# controller.net
KiCad netlist of a schematic drawn in EAGLE
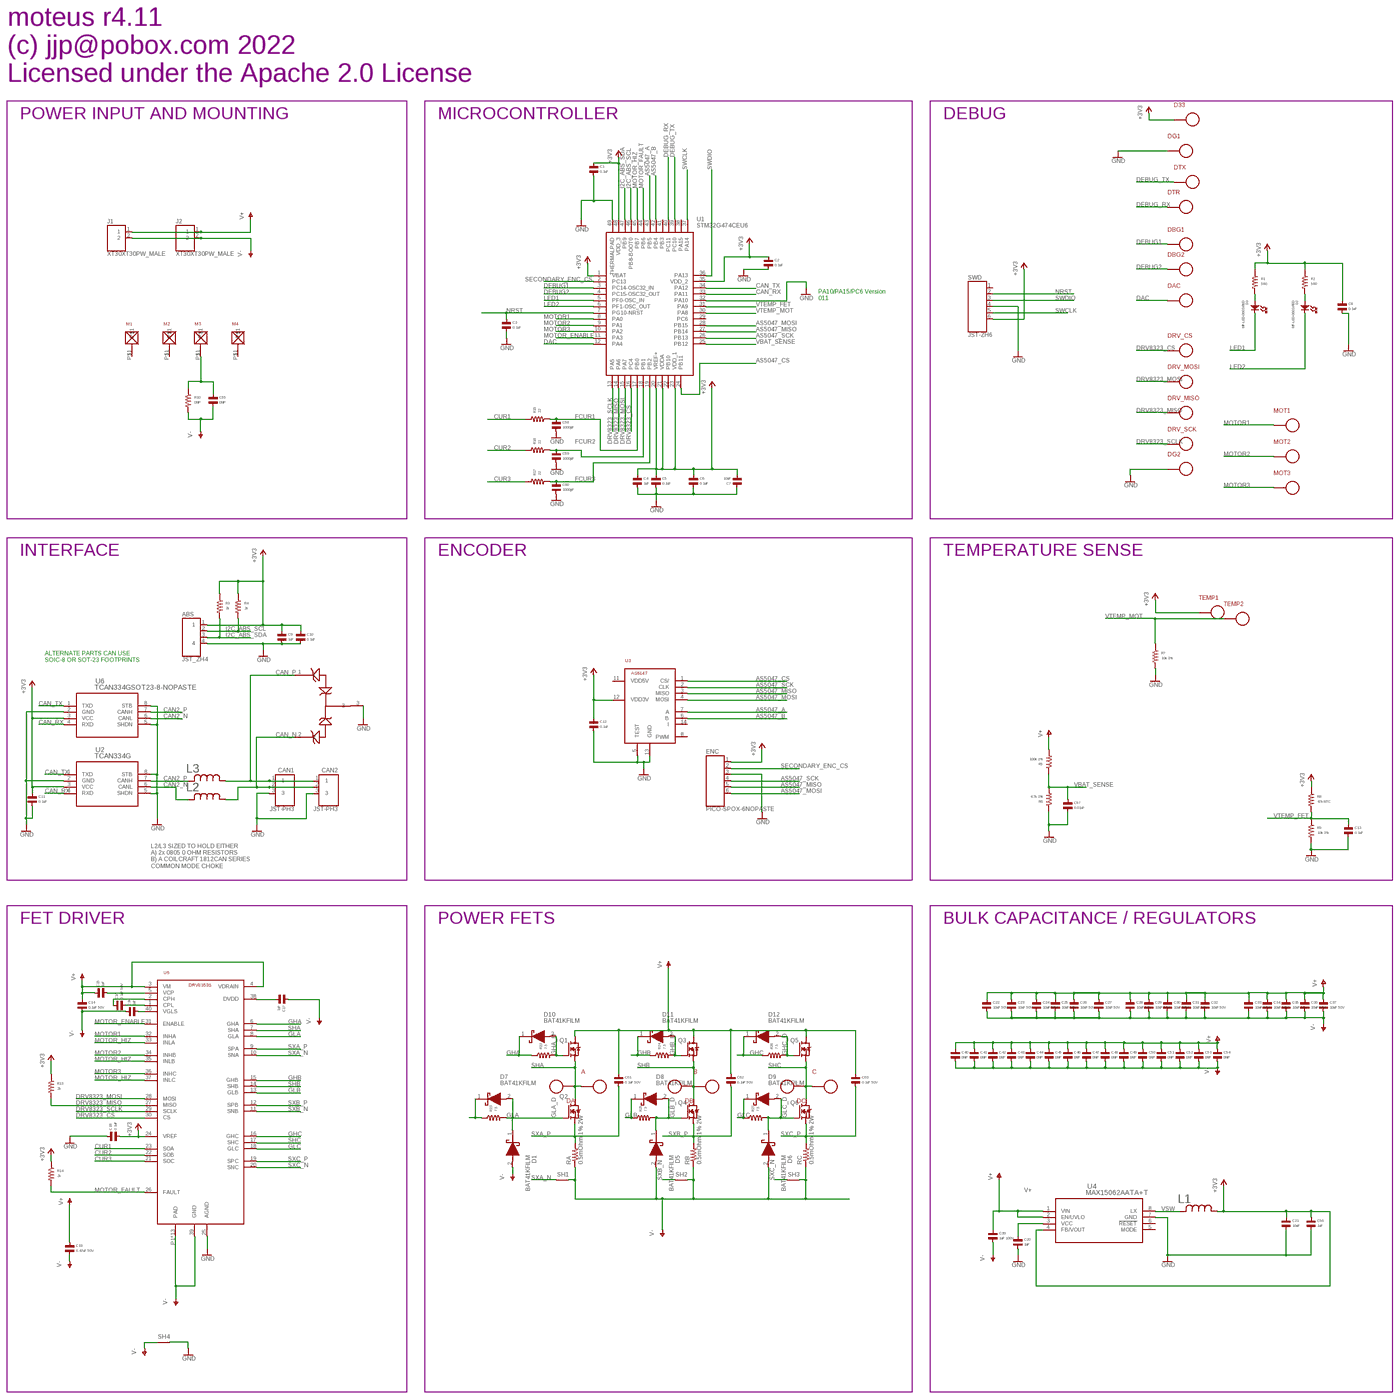
[diagram p0: schematic, sheet 1, overview]
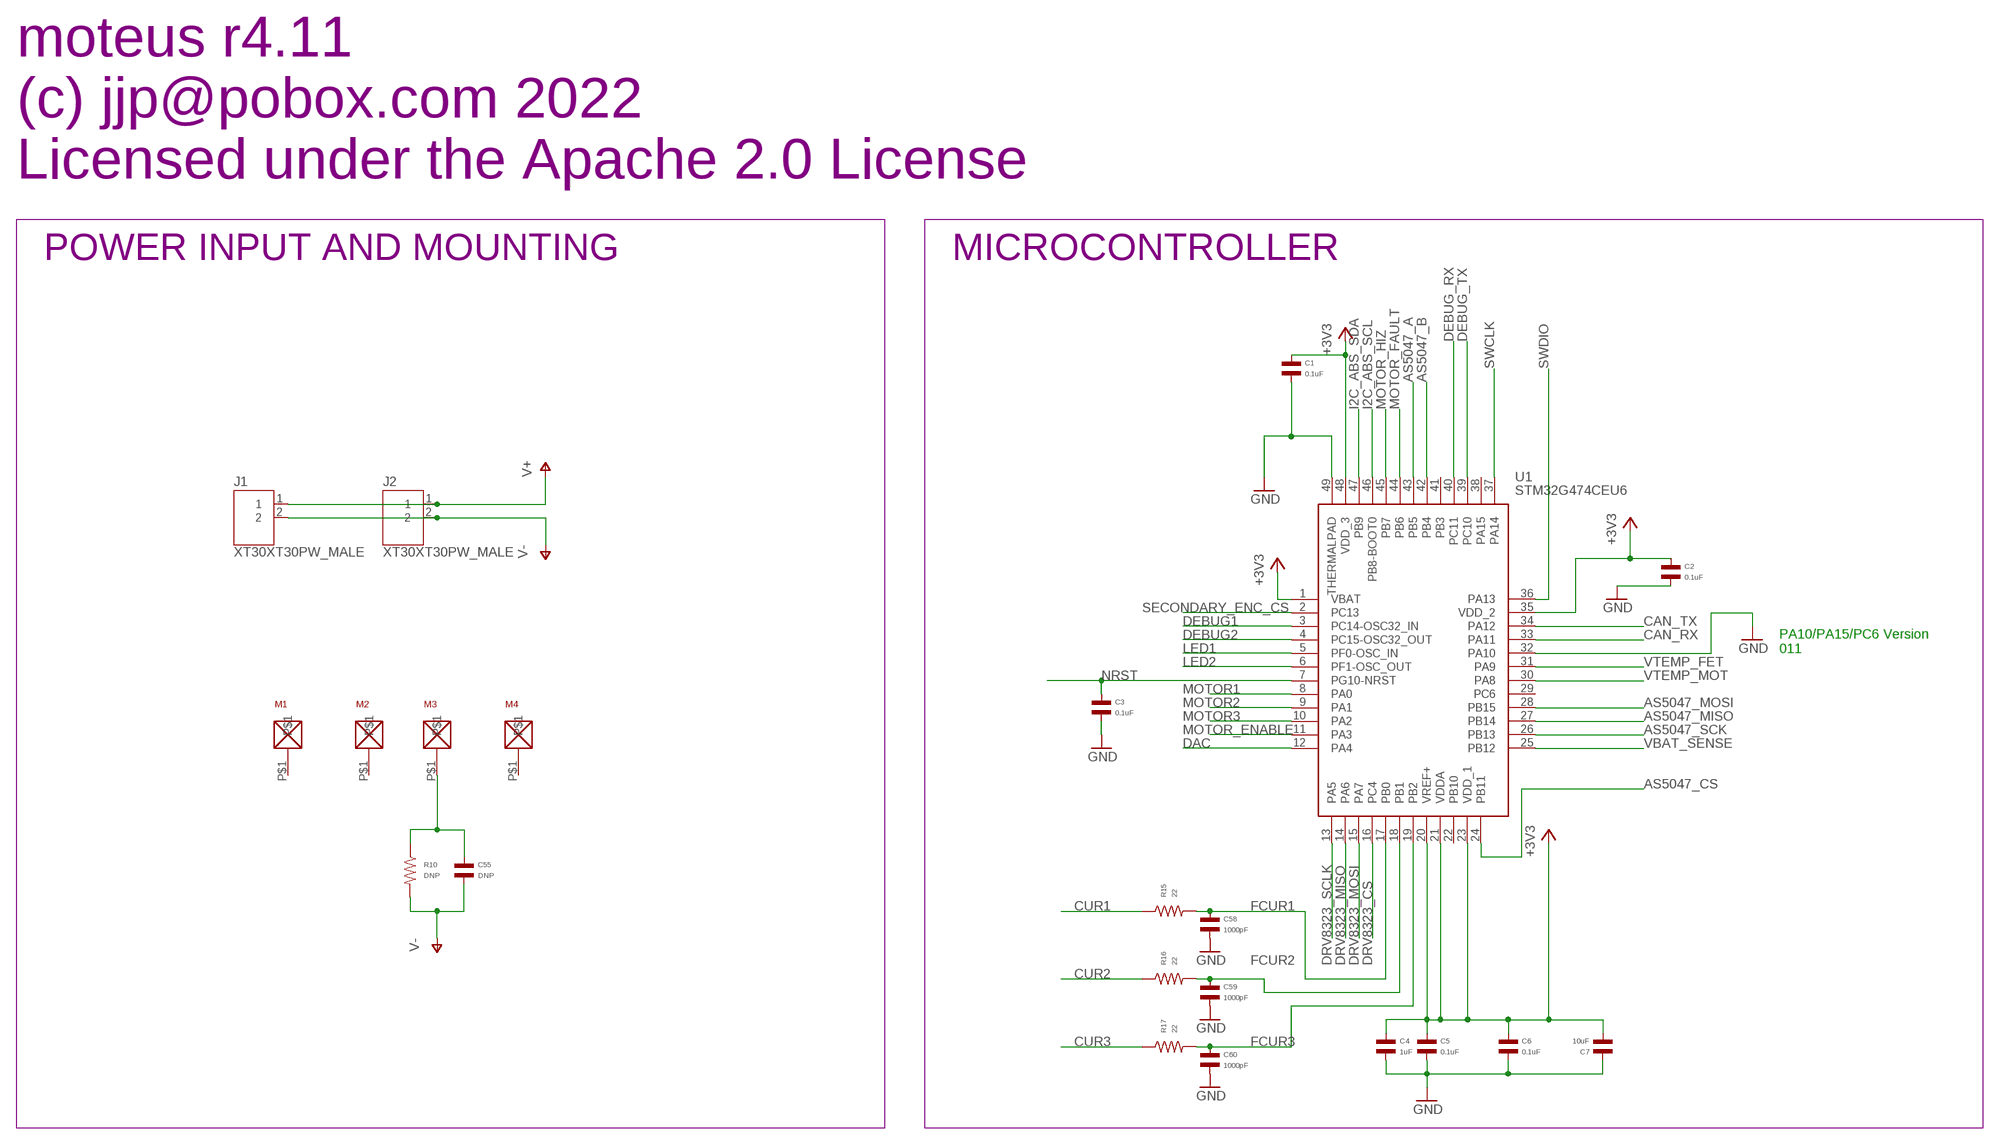
[diagram p1: schematic, sheet 1, part 1 of 4]
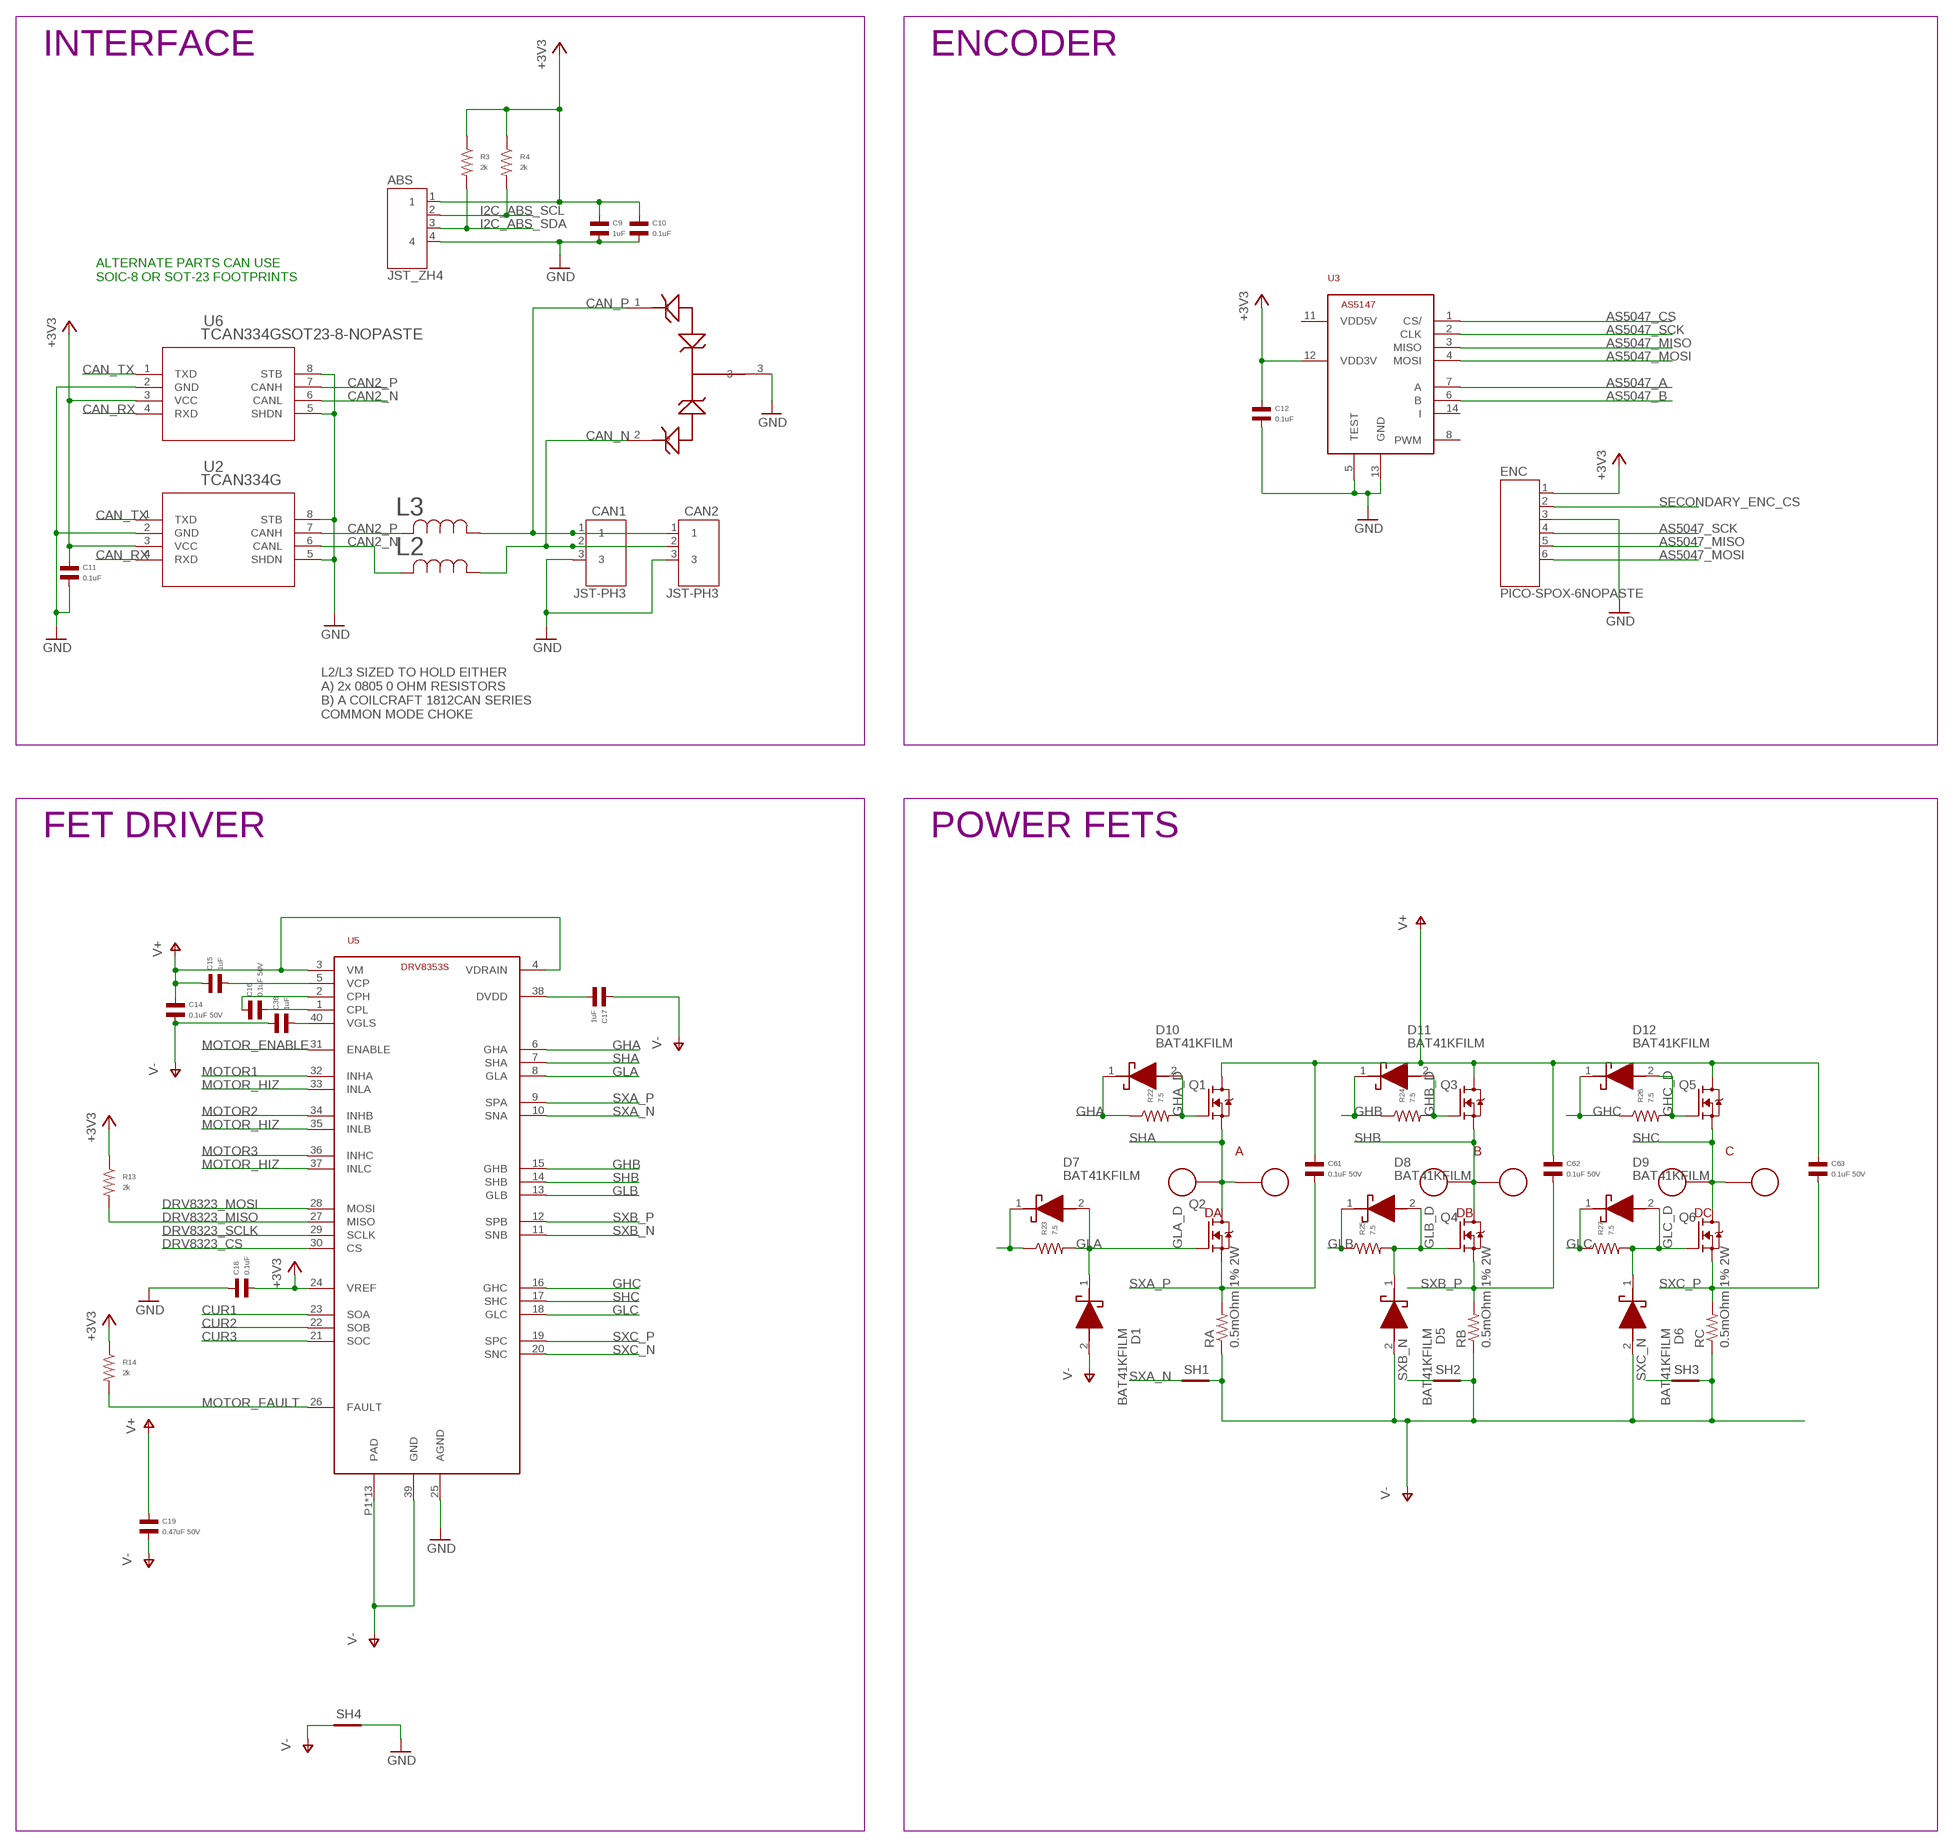
[diagram p2: schematic, sheet 1, part 2 of 4]
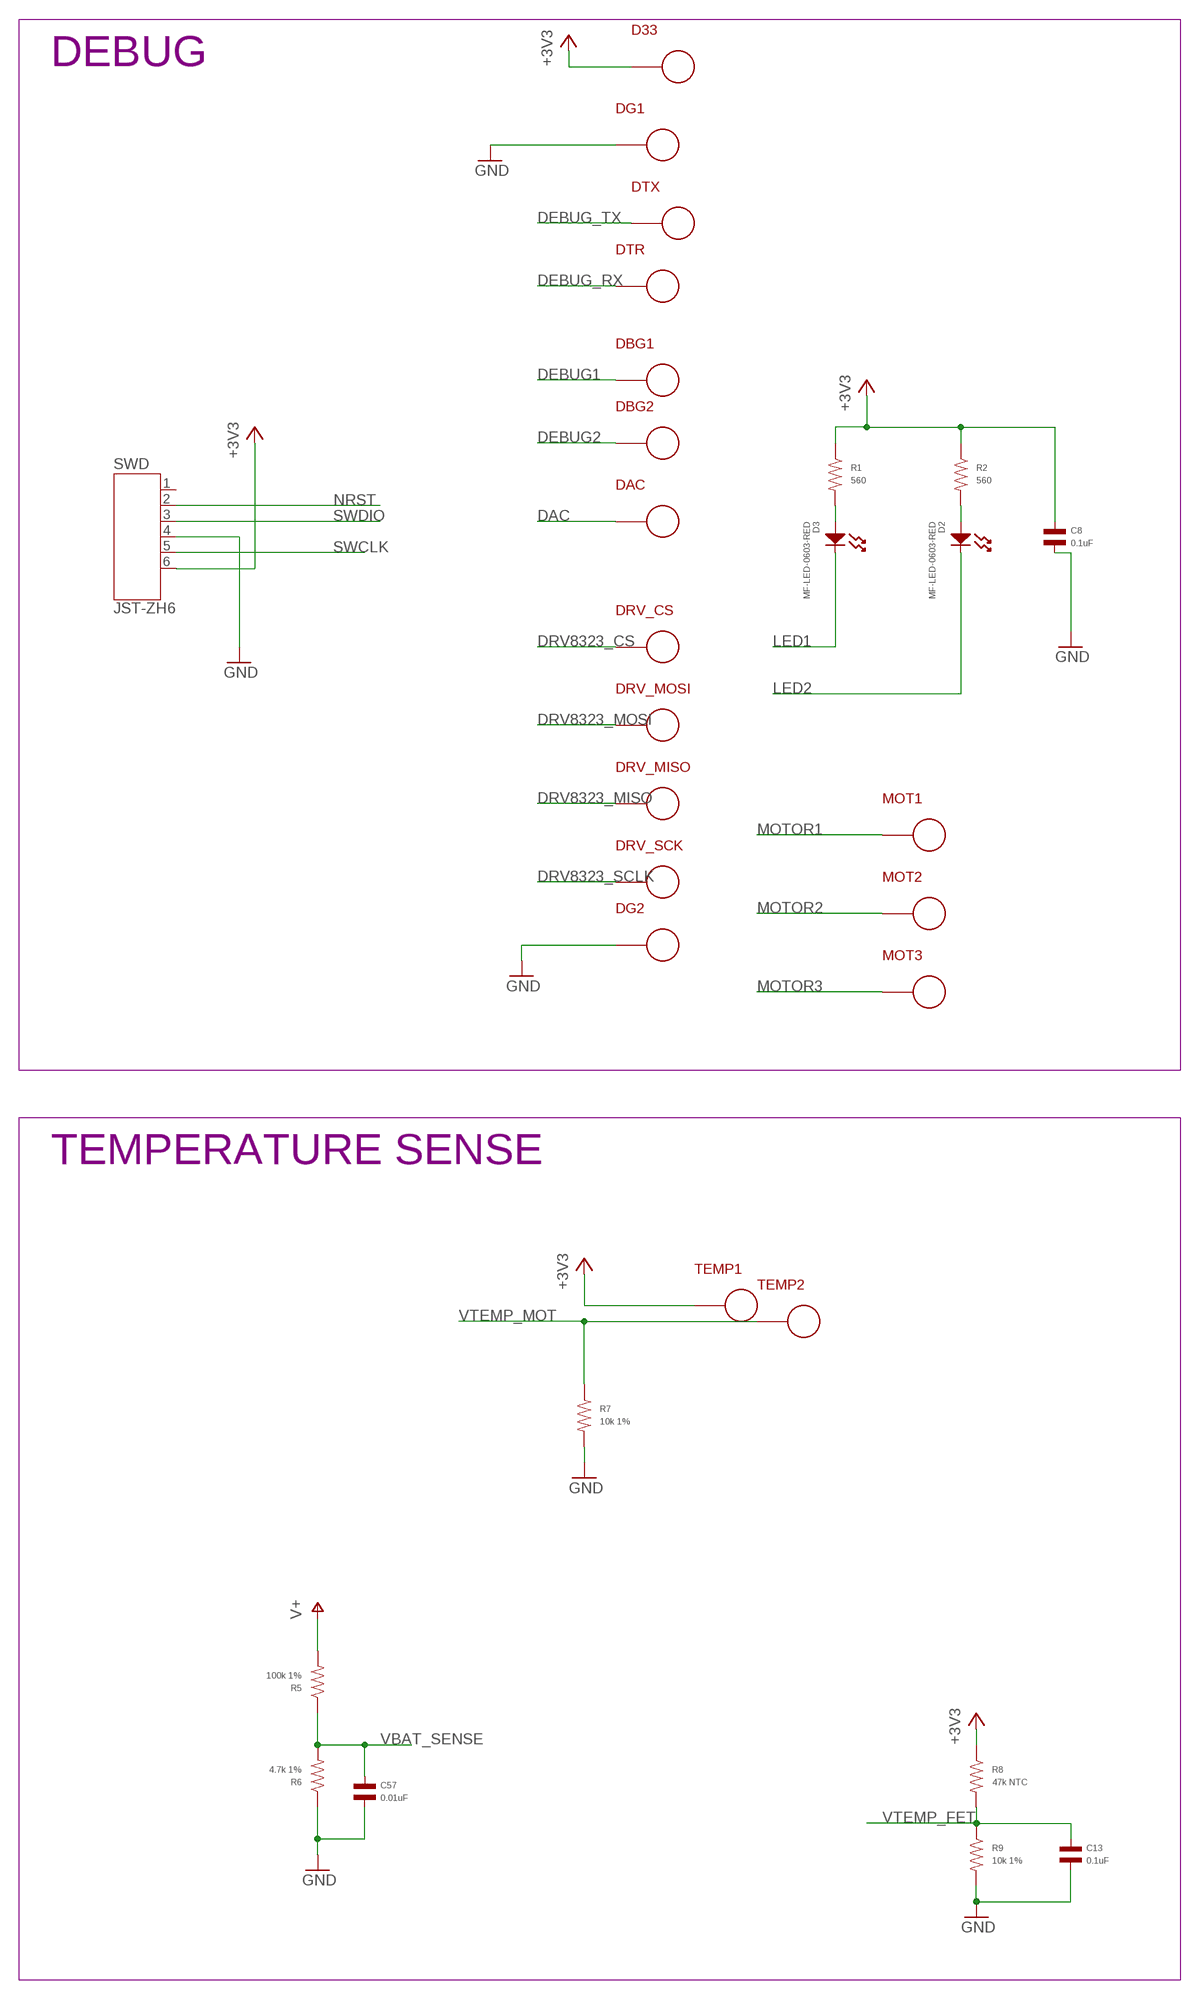
[diagram p3: schematic, sheet 1, part 3 of 4]
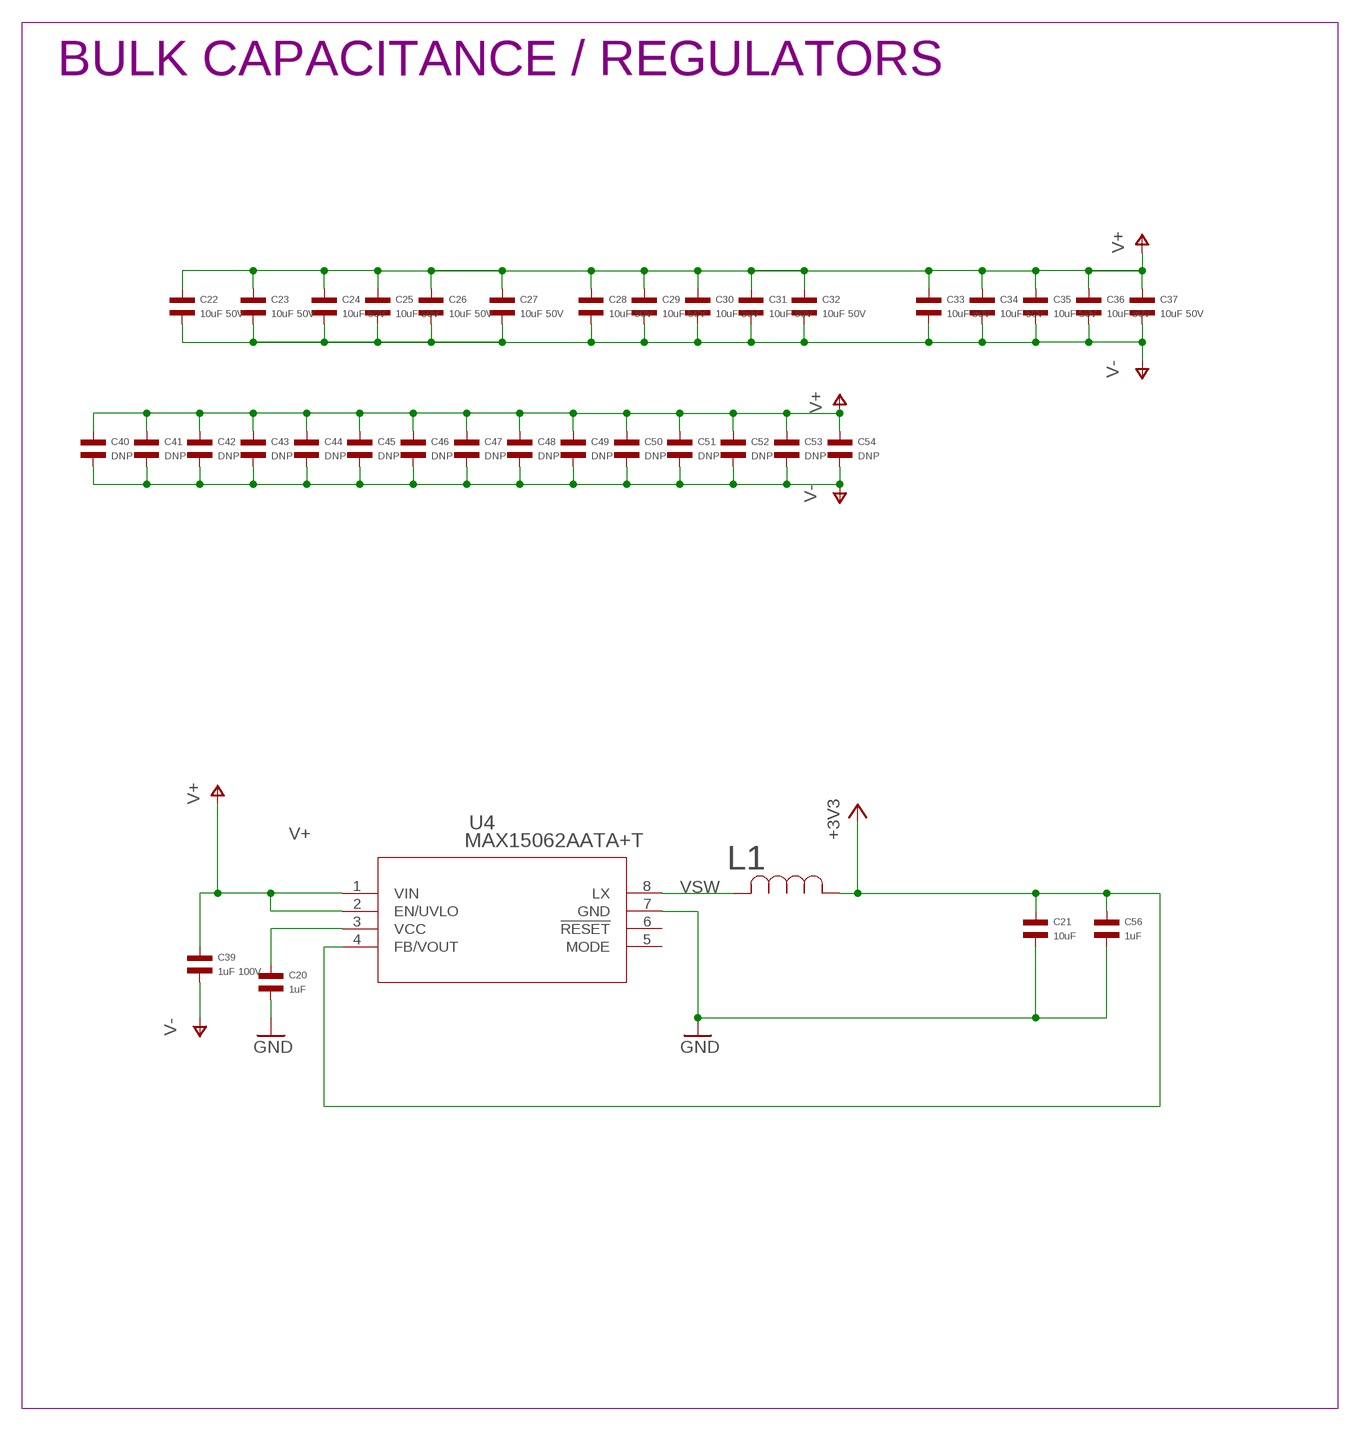
[diagram p4: schematic, sheet 1, part 4 of 4]

(export (version "E")
  (design (tool "Eeschema 10.0.6"))
  (components
    (comp (ref "A")
      (value "PAD16AWG_PAD")
      (footprint "eagle-import:16AWG_PAD")
      (libsource (lib "eagle-import") (part "PAD16AWG_PAD"))
    )
    (comp (ref "ABS")
      (value "JST_ZH4")
      (footprint "eagle-import:JST_S4B-ZR-SM4A-TF(LF)(SN)")
      (fields (field (name "MF") "JST") (field (name "MPN") "S4B-ZR-SM4A-TF(LF)(SN)"))
      (libsource (lib "eagle-import") (part "JST_ZH4"))
    )
    (comp (ref "B")
      (value "PAD16AWG_PAD")
      (footprint "eagle-import:16AWG_PAD")
      (libsource (lib "eagle-import") (part "PAD16AWG_PAD"))
    )
    (comp (ref "C")
      (value "PAD16AWG_PAD")
      (footprint "eagle-import:16AWG_PAD")
      (libsource (lib "eagle-import") (part "PAD16AWG_PAD"))
    )
    (comp (ref "C1")
      (value "0.1uF")
      (footprint "eagle-import:C0402")
      (fields (field (name "HOUSEPART") "YES") (field (name "MPN") "MF-CAP-0402-0.1uF"))
      (libsource (lib "eagle-import") (part "mfpassives_CAPACITOR_NP_0402"))
    )
    (comp (ref "C2")
      (value "0.1uF")
      (footprint "eagle-import:C0402")
      (fields (field (name "HOUSEPART") "YES") (field (name "MPN") "MF-CAP-0402-0.1uF"))
      (libsource (lib "eagle-import") (part "mfpassives_CAPACITOR_NP_0402"))
    )
    (comp (ref "C3")
      (value "0.1uF")
      (footprint "eagle-import:C0402")
      (fields (field (name "HOUSEPART") "YES") (field (name "MPN") "MF-CAP-0402-0.1uF"))
      (libsource (lib "eagle-import") (part "mfpassives_CAPACITOR_NP_0402"))
    )
    (comp (ref "C4")
      (value "1uF")
      (footprint "eagle-import:C0402")
      (fields (field (name "HOUSEPART") "YES") (field (name "MPN") "MF-CAP-0402-1uF"))
      (libsource (lib "eagle-import") (part "mfpassives_CAPACITOR_NP_0402"))
    )
    (comp (ref "C5")
      (value "0.1uF")
      (footprint "eagle-import:C0402")
      (fields (field (name "HOUSEPART") "YES") (field (name "MPN") "MF-CAP-0402-0.1uF"))
      (libsource (lib "eagle-import") (part "mfpassives_CAPACITOR_NP_0402"))
    )
    (comp (ref "C6")
      (value "0.1uF")
      (footprint "eagle-import:C0402")
      (fields (field (name "HOUSEPART") "YES") (field (name "MPN") "MF-CAP-0402-0.1uF"))
      (libsource (lib "eagle-import") (part "mfpassives_CAPACITOR_NP_0402"))
    )
    (comp (ref "C7")
      (value "10uF")
      (footprint "eagle-import:C1206")
      (fields (field (name "HOUSEPART") "YES") (field (name "MPN") "MF-CAP-1206-10uF"))
      (libsource (lib "eagle-import") (part "mfpassives_CAPACITOR_NP_1206"))
    )
    (comp (ref "C8")
      (value "0.1uF")
      (footprint "eagle-import:C0402")
      (fields (field (name "HOUSEPART") "YES") (field (name "MPN") "MF-CAP-0402-0.1uF"))
      (libsource (lib "eagle-import") (part "mfpassives_CAPACITOR_NP_0402"))
    )
    (comp (ref "C9")
      (value "1uF")
      (footprint "eagle-import:C0402")
      (fields (field (name "HOUSEPART") "YES") (field (name "MPN") "MF-CAP-0402-1uF"))
      (libsource (lib "eagle-import") (part "mfpassives_CAPACITOR_NP_0402"))
    )
    (comp (ref "C10")
      (value "0.1uF")
      (footprint "eagle-import:C0402")
      (fields (field (name "HOUSEPART") "YES") (field (name "MPN") "MF-CAP-0402-0.1uF"))
      (libsource (lib "eagle-import") (part "mfpassives_CAPACITOR_NP_0402"))
    )
    (comp (ref "C11")
      (value "0.1uF")
      (footprint "eagle-import:C0402_NOBORDER")
      (fields (field (name "HOUSEPART") "YES") (field (name "MPN") "MF-CAP-0402-0.1uF"))
      (libsource (lib "eagle-import") (part "CAPACITOR_NP_0402_NOBORDER"))
    )
    (comp (ref "C12")
      (value "0.1uF")
      (footprint "eagle-import:C0402")
      (fields (field (name "HOUSEPART") "YES") (field (name "MPN") "MF-CAP-0402-0.1uF"))
      (libsource (lib "eagle-import") (part "mfpassives_CAPACITOR_NP_0402"))
    )
    (comp (ref "C13")
      (value "0.1uF")
      (footprint "eagle-import:C0402")
      (fields (field (name "HOUSEPART") "YES") (field (name "MPN") "MF-CAP-0402-0.1uF"))
      (libsource (lib "eagle-import") (part "mfpassives_CAPACITOR_NP_0402"))
    )
    (comp (ref "C14")
      (value "0.1uF 50V")
      (footprint "eagle-import:C0402")
      (fields (field (name "MF") "TDK") (field (name "MPN") "CGA2B3X7R1H104K050BB"))
      (libsource (lib "eagle-import") (part "mfpassives_CAPACITOR_NP_0402"))
    )
    (comp (ref "C15")
      (value "1uF")
      (footprint "eagle-import:C0402")
      (fields (field (name "HOUSEPART") "YES") (field (name "MPN") "MF-CAP-0402-1uF"))
      (libsource (lib "eagle-import") (part "mfpassives_CAPACITOR_NP_0402"))
    )
    (comp (ref "C16")
      (value "0.1uF 50V")
      (footprint "eagle-import:C0402")
      (fields (field (name "MF") "TDK") (field (name "MPN") "CGA2B3X7R1H104K050BB"))
      (libsource (lib "eagle-import") (part "mfpassives_CAPACITOR_NP_0402"))
    )
    (comp (ref "C17")
      (value "1uF")
      (footprint "eagle-import:C0402")
      (fields (field (name "HOUSEPART") "YES") (field (name "MPN") "MF-CAP-0402-1uF"))
      (libsource (lib "eagle-import") (part "mfpassives_CAPACITOR_NP_0402"))
    )
    (comp (ref "C18")
      (value "0.1uF")
      (footprint "eagle-import:C0402")
      (fields (field (name "HOUSEPART") "YES") (field (name "MPN") "MF-CAP-0402-0.1uF"))
      (libsource (lib "eagle-import") (part "mfpassives_CAPACITOR_NP_0402"))
    )
    (comp (ref "C19")
      (value "0.47uF 50V")
      (footprint "eagle-import:C0402")
      (fields (field (name "MF") "Murata") (field (name "MPN") "GRM155R61H474KE11D"))
      (libsource (lib "eagle-import") (part "mfpassives_CAPACITOR_NP_0402"))
    )
    (comp (ref "C20")
      (value "1uF")
      (footprint "eagle-import:C0603")
      (fields (field (name "HOUSEPART") "1") (field (name "MPN") "MF-CAP-0603-1uF"))
      (libsource (lib "eagle-import") (part "mfpassives_CAPACITOR_NP_0603"))
    )
    (comp (ref "C21")
      (value "10uF")
      (footprint "eagle-import:C1206")
      (fields (field (name "HOUSEPART") "1") (field (name "MPN") "MF-CAP-1206-10uF"))
      (libsource (lib "eagle-import") (part "mfpassives_CAPACITOR_NP_1206"))
    )
    (comp (ref "C22")
      (value "10uF 50V")
      (footprint "eagle-import:C1206")
      (fields (field (name "MF") "TDK") (field (name "MPN") "C3216X7R1H106K160AE"))
      (libsource (lib "eagle-import") (part "mfpassives_CAPACITOR_NP_1206"))
    )
    (comp (ref "C23")
      (value "10uF 50V")
      (footprint "eagle-import:C1206")
      (fields (field (name "MF") "TDK") (field (name "MPN") "C3216X7R1H106K160AE"))
      (libsource (lib "eagle-import") (part "mfpassives_CAPACITOR_NP_1206"))
    )
    (comp (ref "C24")
      (value "10uF 50V")
      (footprint "eagle-import:C1206")
      (fields (field (name "MF") "TDK") (field (name "MPN") "C3216X7R1H106K160AE"))
      (libsource (lib "eagle-import") (part "mfpassives_CAPACITOR_NP_1206"))
    )
    (comp (ref "C25")
      (value "10uF 50V")
      (footprint "eagle-import:C1206")
      (fields (field (name "MF") "TDK") (field (name "MPN") "C3216X7R1H106K160AE"))
      (libsource (lib "eagle-import") (part "mfpassives_CAPACITOR_NP_1206"))
    )
    (comp (ref "C26")
      (value "10uF 50V")
      (footprint "eagle-import:C1206")
      (fields (field (name "MF") "TDK") (field (name "MPN") "C3216X7R1H106K160AE"))
      (libsource (lib "eagle-import") (part "mfpassives_CAPACITOR_NP_1206"))
    )
    (comp (ref "C27")
      (value "10uF 50V")
      (footprint "eagle-import:C1206")
      (fields (field (name "MF") "TDK") (field (name "MPN") "C3216X7R1H106K160AE"))
      (libsource (lib "eagle-import") (part "mfpassives_CAPACITOR_NP_1206"))
    )
    (comp (ref "C28")
      (value "10uF 50V")
      (footprint "eagle-import:C1206")
      (fields (field (name "MF") "TDK") (field (name "MPN") "C3216X7R1H106K160AE"))
      (libsource (lib "eagle-import") (part "mfpassives_CAPACITOR_NP_1206"))
    )
    (comp (ref "C29")
      (value "10uF 50V")
      (footprint "eagle-import:C1206")
      (fields (field (name "MF") "TDK") (field (name "MPN") "C3216X7R1H106K160AE"))
      (libsource (lib "eagle-import") (part "mfpassives_CAPACITOR_NP_1206"))
    )
    (comp (ref "C30")
      (value "10uF 50V")
      (footprint "eagle-import:C1206")
      (fields (field (name "MF") "TDK") (field (name "MPN") "C3216X7R1H106K160AE"))
      (libsource (lib "eagle-import") (part "mfpassives_CAPACITOR_NP_1206"))
    )
    (comp (ref "C31")
      (value "10uF 50V")
      (footprint "eagle-import:C1206")
      (fields (field (name "MF") "TDK") (field (name "MPN") "C3216X7R1H106K160AE"))
      (libsource (lib "eagle-import") (part "mfpassives_CAPACITOR_NP_1206"))
    )
    (comp (ref "C32")
      (value "10uF 50V")
      (footprint "eagle-import:C1206")
      (fields (field (name "MF") "TDK") (field (name "MPN") "C3216X7R1H106K160AE"))
      (libsource (lib "eagle-import") (part "mfpassives_CAPACITOR_NP_1206"))
    )
    (comp (ref "C33")
      (value "10uF 50V")
      (footprint "eagle-import:C1206")
      (fields (field (name "MF") "TDK") (field (name "MPN") "C3216X7R1H106K160AE"))
      (libsource (lib "eagle-import") (part "mfpassives_CAPACITOR_NP_1206"))
    )
    (comp (ref "C34")
      (value "10uF 50V")
      (footprint "eagle-import:C1206")
      (fields (field (name "MF") "TDK") (field (name "MPN") "C3216X7R1H106K160AE"))
      (libsource (lib "eagle-import") (part "mfpassives_CAPACITOR_NP_1206"))
    )
    (comp (ref "C35")
      (value "10uF 50V")
      (footprint "eagle-import:C1206_NOBORDER")
      (fields (field (name "MF") "TDK") (field (name "MPN") "C3216X7R1H106K160AE"))
      (libsource (lib "eagle-import") (part "CAPACITOR_NP_1206_NOBORDER"))
    )
    (comp (ref "C36")
      (value "10uF 50V")
      (footprint "eagle-import:C1206")
      (fields (field (name "MF") "TDK") (field (name "MPN") "C3216X7R1H106K160AE"))
      (libsource (lib "eagle-import") (part "mfpassives_CAPACITOR_NP_1206"))
    )
    (comp (ref "C37")
      (value "10uF 50V")
      (footprint "eagle-import:C1206")
      (fields (field (name "MF") "TDK") (field (name "MPN") "C3216X7R1H106K160AE"))
      (libsource (lib "eagle-import") (part "mfpassives_CAPACITOR_NP_1206"))
    )
    (comp (ref "C38")
      (value "1uF")
      (footprint "eagle-import:C0603")
      (fields
        (field (name "HOUSEPART") "YES")
        (field (name "MF") "TDK")
        (field (name "MPN") "C1608X7R1E105K080AE")
      )
      (libsource (lib "eagle-import") (part "mfpassives_CAPACITOR_NP_0603"))
    )
    (comp (ref "C39")
      (value "1uF 100V")
      (footprint "eagle-import:C0805")
      (fields (field (name "MF") "MURATA") (field (name "MPN") "GCM21BC72A105KE36L"))
      (libsource (lib "eagle-import") (part "mfpassives_CAPACITOR_NP_0805"))
    )
    (comp (ref "C40")
      (value "DNP")
      (footprint "eagle-import:C1206_NOCREAM")
      (libsource (lib "eagle-import") (part "CAPACITOR_NP_1206_NOCREAM"))
    )
    (comp (ref "C41")
      (value "DNP")
      (footprint "eagle-import:C1206_NOCREAM")
      (libsource (lib "eagle-import") (part "CAPACITOR_NP_1206_NOCREAM"))
    )
    (comp (ref "C42")
      (value "DNP")
      (footprint "eagle-import:C1206_NOCREAM")
      (libsource (lib "eagle-import") (part "CAPACITOR_NP_1206_NOCREAM"))
    )
    (comp (ref "C43")
      (value "DNP")
      (footprint "eagle-import:C1206_NOCREAM")
      (libsource (lib "eagle-import") (part "CAPACITOR_NP_1206_NOCREAM"))
    )
    (comp (ref "C44")
      (value "DNP")
      (footprint "eagle-import:C1206_NOCREAM")
      (libsource (lib "eagle-import") (part "CAPACITOR_NP_1206_NOCREAM"))
    )
    (comp (ref "C45")
      (value "DNP")
      (footprint "eagle-import:C1206_NOCREAM")
      (libsource (lib "eagle-import") (part "CAPACITOR_NP_1206_NOCREAM"))
    )
    (comp (ref "C46")
      (value "DNP")
      (footprint "eagle-import:C1206_NOCREAM")
      (libsource (lib "eagle-import") (part "CAPACITOR_NP_1206_NOCREAM"))
    )
    (comp (ref "C47")
      (value "DNP")
      (footprint "eagle-import:C1206_NOCREAM")
      (libsource (lib "eagle-import") (part "CAPACITOR_NP_1206_NOCREAM"))
    )
    (comp (ref "C48")
      (value "DNP")
      (footprint "eagle-import:C1206_NOCREAM")
      (libsource (lib "eagle-import") (part "CAPACITOR_NP_1206_NOCREAM"))
    )
    (comp (ref "C49")
      (value "DNP")
      (footprint "eagle-import:C1206_NOCREAM")
      (libsource (lib "eagle-import") (part "CAPACITOR_NP_1206_NOCREAM"))
    )
    (comp (ref "C50")
      (value "DNP")
      (footprint "eagle-import:C1206_NOCREAM")
      (libsource (lib "eagle-import") (part "CAPACITOR_NP_1206_NOCREAM"))
    )
    (comp (ref "C51")
      (value "DNP")
      (footprint "eagle-import:C1206_NOCREAM")
      (libsource (lib "eagle-import") (part "CAPACITOR_NP_1206_NOCREAM"))
    )
    (comp (ref "C52")
      (value "DNP")
      (footprint "eagle-import:C1206_NOCREAM")
      (libsource (lib "eagle-import") (part "CAPACITOR_NP_1206_NOCREAM"))
    )
    (comp (ref "C53")
      (value "DNP")
      (footprint "eagle-import:C1206_NOCREAM")
      (libsource (lib "eagle-import") (part "CAPACITOR_NP_1206_NOCREAM"))
    )
    (comp (ref "C54")
      (value "DNP")
      (footprint "eagle-import:C1206_NOCREAM")
      (libsource (lib "eagle-import") (part "CAPACITOR_NP_1206_NOCREAM"))
    )
    (comp (ref "C55")
      (value "DNP")
      (footprint "eagle-import:C0402")
      (fields (field (name "POPULATE") "0"))
      (libsource (lib "eagle-import") (part "mfpassives_CAPACITOR_NP_0402"))
    )
    (comp (ref "C56")
      (value "1uF")
      (footprint "eagle-import:C0402")
      (fields (field (name "HOUSEPART") "YES") (field (name "MPN") "MF-CAP-0402-1uF"))
      (libsource (lib "eagle-import") (part "mfpassives_CAPACITOR_NP_0402"))
    )
    (comp (ref "C57")
      (value "0.01uF")
      (footprint "eagle-import:C0402")
      (fields (field (name "HOUSEPART") "YES") (field (name "MPN") "MF-CAP-0402-0.01uF"))
      (libsource (lib "eagle-import") (part "mfpassives_CAPACITOR_NP_0402"))
    )
    (comp (ref "C58")
      (value "1000pF")
      (footprint "eagle-import:C0402_NOBORDER")
      (fields (field (name "HOUSEPART") "1") (field (name "MPN") "MF-CAP-0402-1nF"))
      (libsource (lib "eagle-import") (part "CAPACITOR_NP_0402_NOBORDER"))
    )
    (comp (ref "C59")
      (value "1000pF")
      (footprint "eagle-import:C0402_NOBORDER")
      (fields (field (name "HOUSEPART") "1") (field (name "MPN") "MF-CAP-0402-1nF"))
      (libsource (lib "eagle-import") (part "CAPACITOR_NP_0402_NOBORDER"))
    )
    (comp (ref "C60")
      (value "1000pF")
      (footprint "eagle-import:C0402_NOBORDER")
      (fields (field (name "HOUSEPART") "1") (field (name "MPN") "MF-CAP-0402-1nF"))
      (libsource (lib "eagle-import") (part "CAPACITOR_NP_0402_NOBORDER"))
    )
    (comp (ref "C61")
      (value "0.1uF 50V")
      (footprint "eagle-import:C1206")
      (fields (field (name "MF") "KYOCERA AVX") (field (name "MPN") "12065C104KAZ2A"))
      (libsource (lib "eagle-import") (part "mfpassives_CAPACITOR_NP_1206"))
    )
    (comp (ref "C62")
      (value "0.1uF 50V")
      (footprint "eagle-import:C0603_NOBORDER")
      (fields (field (name "MF") "KYOCERA AVX") (field (name "MPN") "06035C104KAZ2A"))
      (libsource (lib "eagle-import") (part "CAPACITOR_NP_0603_NOBORDER"))
    )
    (comp (ref "C63")
      (value "0.1uF 50V")
      (footprint "eagle-import:C1206")
      (fields (field (name "MF") "KYOCERA AVX") (field (name "MPN") "12065C104KAZ2A"))
      (libsource (lib "eagle-import") (part "mfpassives_CAPACITOR_NP_1206"))
    )
    (comp (ref "CAN1")
      (value "JST-PH3")
      (footprint "eagle-import:JST_S3B-PH-SM4-TB(LF)(SN)")
      (fields (field (name "MF") "JST") (field (name "MPN") "S3B-PH-SM4-TB(LF)(SN)"))
      (libsource (lib "eagle-import") (part "JST-PH3"))
    )
    (comp (ref "CAN2")
      (value "JST-PH3")
      (footprint "eagle-import:JST_S3B-PH-SM4-TB(LF)(SN)")
      (fields (field (name "MF") "JST") (field (name "MPN") "S3B-PH-SM4-TB(LF)(SN)"))
      (libsource (lib "eagle-import") (part "JST-PH3"))
    )
    (comp (ref "D1")
      (value "BAT41KFILM")
      (footprint "eagle-import:SODFL1608X70N")
      (fields (field (name "MOUSER_PART_NUMBER") "511-BAT41KFILM") (field (name "MF") "ST"))
      (libsource (lib "eagle-import") (part "BAT41KFILM"))
    )
    (comp (ref "D2")
      (value "MF-LED-0603-RED")
      (footprint "eagle-import:LED0603")
      (fields (field (name "HOUSEPART") "YES") (field (name "MPN") "MF-LED-0603-GREEN"))
      (libsource (lib "eagle-import") (part "LED_SINGLE-0603-RED"))
    )
    (comp (ref "D3")
      (value "MF-LED-0603-RED")
      (footprint "eagle-import:LED0603")
      (fields (field (name "HOUSEPART") "YES"))
      (libsource (lib "eagle-import") (part "LED_SINGLE-0603-RED"))
    )
    (comp (ref "D4")
      (value "DUAL_TVS")
      (footprint "eagle-import:SOT23-3")
      (fields (field (name "MPN") "CDSOT23-0502B"))
      (libsource (lib "eagle-import") (part "DUAL_TVS"))
    )
    (comp (ref "D5")
      (value "BAT41KFILM")
      (footprint "eagle-import:SODFL1608X70N")
      (fields (field (name "MOUSER_PART_NUMBER") "511-BAT41KFILM") (field (name "MF") "ST"))
      (libsource (lib "eagle-import") (part "BAT41KFILM"))
    )
    (comp (ref "D6")
      (value "BAT41KFILM")
      (footprint "eagle-import:SODFL1608X70N")
      (fields (field (name "MOUSER_PART_NUMBER") "511-BAT41KFILM") (field (name "MF") "ST"))
      (libsource (lib "eagle-import") (part "BAT41KFILM"))
    )
    (comp (ref "D7")
      (value "BAT41KFILM")
      (footprint "eagle-import:SODFL1608X70N")
      (fields (field (name "MOUSER_PART_NUMBER") "511-BAT41KFILM") (field (name "MF") "ST"))
      (libsource (lib "eagle-import") (part "BAT41KFILM"))
    )
    (comp (ref "D8")
      (value "BAT41KFILM")
      (footprint "eagle-import:SODFL1608X70N")
      (fields (field (name "MOUSER_PART_NUMBER") "511-BAT41KFILM") (field (name "MF") "ST"))
      (libsource (lib "eagle-import") (part "BAT41KFILM"))
    )
    (comp (ref "D9")
      (value "BAT41KFILM")
      (footprint "eagle-import:SODFL1608X70N")
      (fields (field (name "MOUSER_PART_NUMBER") "511-BAT41KFILM") (field (name "MF") "ST"))
      (libsource (lib "eagle-import") (part "BAT41KFILM"))
    )
    (comp (ref "D10")
      (value "BAT41KFILM")
      (footprint "eagle-import:SODFL1608X70N")
      (fields (field (name "MOUSER_PART_NUMBER") "511-BAT41KFILM") (field (name "MF") "ST"))
      (libsource (lib "eagle-import") (part "BAT41KFILM"))
    )
    (comp (ref "D11")
      (value "BAT41KFILM")
      (footprint "eagle-import:SODFL1608X70N")
      (fields (field (name "MOUSER_PART_NUMBER") "511-BAT41KFILM") (field (name "MF") "ST"))
      (libsource (lib "eagle-import") (part "BAT41KFILM"))
    )
    (comp (ref "D12")
      (value "BAT41KFILM")
      (footprint "eagle-import:SODFL1608X70N")
      (fields (field (name "MOUSER_PART_NUMBER") "511-BAT41KFILM") (field (name "MF") "ST"))
      (libsource (lib "eagle-import") (part "BAT41KFILM"))
    )
    (comp (ref "D33")
      (value "PAD24AWG_PAD")
      (footprint "eagle-import:24AWG_PAD")
      (libsource (lib "eagle-import") (part "PAD24AWG_PAD"))
    )
    (comp (ref "DA")
      (value "PAD24AWG_PAD")
      (footprint "eagle-import:24AWG_PAD")
      (libsource (lib "eagle-import") (part "PAD24AWG_PAD"))
    )
    (comp (ref "DAC")
      (value "PAD24AWG_PAD")
      (footprint "eagle-import:24AWG_PAD")
      (libsource (lib "eagle-import") (part "PAD24AWG_PAD"))
    )
    (comp (ref "DB")
      (value "PAD24AWG_PAD")
      (footprint "eagle-import:24AWG_PAD")
      (libsource (lib "eagle-import") (part "PAD24AWG_PAD"))
    )
    (comp (ref "DBG1")
      (value "PAD24AWG_PAD")
      (footprint "eagle-import:24AWG_PAD")
      (libsource (lib "eagle-import") (part "PAD24AWG_PAD"))
    )
    (comp (ref "DBG2")
      (value "PAD24AWG_PAD")
      (footprint "eagle-import:24AWG_PAD")
      (libsource (lib "eagle-import") (part "PAD24AWG_PAD"))
    )
    (comp (ref "DC")
      (value "PAD24AWG_PAD")
      (footprint "eagle-import:24AWG_PAD")
      (libsource (lib "eagle-import") (part "PAD24AWG_PAD"))
    )
    (comp (ref "DG1")
      (value "PAD24AWG_PAD")
      (footprint "eagle-import:24AWG_PAD")
      (libsource (lib "eagle-import") (part "PAD24AWG_PAD"))
    )
    (comp (ref "DG2")
      (value "PAD24AWG_PAD")
      (footprint "eagle-import:24AWG_PAD")
      (libsource (lib "eagle-import") (part "PAD24AWG_PAD"))
    )
    (comp (ref "DRV_CS")
      (value "PAD24AWG_PAD")
      (footprint "eagle-import:24AWG_PAD")
      (libsource (lib "eagle-import") (part "PAD24AWG_PAD"))
    )
    (comp (ref "DRV_MISO")
      (value "PAD24AWG_PAD")
      (footprint "eagle-import:24AWG_PAD")
      (libsource (lib "eagle-import") (part "PAD24AWG_PAD"))
    )
    (comp (ref "DRV_MOSI")
      (value "PAD24AWG_PAD")
      (footprint "eagle-import:24AWG_PAD")
      (libsource (lib "eagle-import") (part "PAD24AWG_PAD"))
    )
    (comp (ref "DRV_SCK")
      (value "PAD24AWG_PAD")
      (footprint "eagle-import:24AWG_PAD")
      (libsource (lib "eagle-import") (part "PAD24AWG_PAD"))
    )
    (comp (ref "DTR")
      (value "PAD24AWG_PAD")
      (footprint "eagle-import:24AWG_PAD")
      (libsource (lib "eagle-import") (part "PAD24AWG_PAD"))
    )
    (comp (ref "DTX")
      (value "PAD24AWG_PAD")
      (footprint "eagle-import:24AWG_PAD")
      (libsource (lib "eagle-import") (part "PAD24AWG_PAD"))
    )
    (comp (ref "ENC")
      (value "PICO-SPOX-6NOPASTE")
      (footprint "eagle-import:PICO-SPOX-SMT-RA-6-NOPASTE")
      (libsource (lib "eagle-import") (part "PICO-SPOX-6NOPASTE"))
    )
    (comp (ref "J1")
      (value "XT30XT30PW_MALE")
      (footprint "eagle-import:XT30PW_MALE")
      (libsource (lib "eagle-import") (part "XT30XT30PW_MALE"))
    )
    (comp (ref "J2")
      (value "XT30XT30PW_MALE")
      (footprint "eagle-import:XT30PW_MALE")
      (libsource (lib "eagle-import") (part "XT30XT30PW_MALE"))
    )
    (comp (ref "L1")
      (value "SRN4018-220M")
      (footprint "eagle-import:IND_BOURNS_SRN4018")
      (fields
        (field (name "MANUFACTURER_PART_NUMBER") "SRN4018220M")
        (field (name "MANUFACTURER_PART_NUMBER_1") "SRN4018-330M")
        (field (name "MPN") "SRN4018-330M")
      )
      (libsource (lib "eagle-import") (part "SRN4018-220M"))
    )
    (comp (ref "L2")
      (value "HALF_CHOKE")
      (footprint "eagle-import:1812_COMMON_HALF")
      (fields (field (name "MPN") "MF-RES-0805-0"))
      (libsource (lib "eagle-import") (part "HALF_CHOKE"))
    )
    (comp (ref "L3")
      (value "HALF_CHOKE")
      (footprint "eagle-import:1812_COMMON_HALF")
      (fields (field (name "MPN") "MF-RES-0805-0"))
      (libsource (lib "eagle-import") (part "HALF_CHOKE"))
    )
    (comp (ref "M1")
      (value "MOUNT")
      (footprint "eagle-import:M2.5MOUNT")
      (libsource (lib "eagle-import") (part "MOUNT"))
    )
    (comp (ref "M2")
      (value "MOUNT")
      (footprint "eagle-import:M2.5MOUNT")
      (libsource (lib "eagle-import") (part "MOUNT"))
    )
    (comp (ref "M3")
      (value "MOUNT")
      (footprint "eagle-import:M2.5MOUNT")
      (libsource (lib "eagle-import") (part "MOUNT"))
    )
    (comp (ref "M4")
      (value "MOUNT")
      (footprint "eagle-import:M2.5MOUNT")
      (libsource (lib "eagle-import") (part "MOUNT"))
    )
    (comp (ref "MOT1")
      (value "PAD24AWG_PAD")
      (footprint "eagle-import:24AWG_PAD")
      (libsource (lib "eagle-import") (part "PAD24AWG_PAD"))
    )
    (comp (ref "MOT2")
      (value "PAD24AWG_PAD")
      (footprint "eagle-import:24AWG_PAD")
      (libsource (lib "eagle-import") (part "PAD24AWG_PAD"))
    )
    (comp (ref "MOT3")
      (value "PAD24AWG_PAD")
      (footprint "eagle-import:24AWG_PAD")
      (libsource (lib "eagle-import") (part "PAD24AWG_PAD"))
    )
    (comp (ref "Q1")
      (value "TPH1R204PLSOP_ADVANCE_8")
      (footprint "eagle-import:SOP_ADVANCE_8")
      (fields
        (field (name "MF") "Toshiba")
        (field (name "MPN") "TPH1R204PL")
        (field (name "MF_1") "Toshiba")
        (field (name "MPN_1") "TPH2R506PL,L1Q")
      )
      (libsource (lib "eagle-import") (part "TPH1R204PLSOP_ADVANCE_8"))
    )
    (comp (ref "Q2")
      (value "TPH1R204PLSOP_ADVANCE_8")
      (footprint "eagle-import:SOP_ADVANCE_8")
      (fields
        (field (name "MF") "Toshiba")
        (field (name "MPN") "TPH1R204PL")
        (field (name "MF_1") "Toshiba")
        (field (name "MPN_1") "TPH2R506PL,L1Q")
      )
      (libsource (lib "eagle-import") (part "TPH1R204PLSOP_ADVANCE_8"))
    )
    (comp (ref "Q3")
      (value "TPH1R204PLSOP_ADVANCE_8")
      (footprint "eagle-import:SOP_ADVANCE_8")
      (fields
        (field (name "MF") "Toshiba")
        (field (name "MPN") "TPH1R204PL")
        (field (name "MF_1") "Toshiba")
        (field (name "MPN_1") "TPH2R506PL,L1Q")
      )
      (libsource (lib "eagle-import") (part "TPH1R204PLSOP_ADVANCE_8"))
    )
    (comp (ref "Q4")
      (value "TPH1R204PLSOP_ADVANCE_8")
      (footprint "eagle-import:SOP_ADVANCE_8")
      (fields
        (field (name "MF") "Toshiba")
        (field (name "MPN") "TPH1R204PL")
        (field (name "MF_1") "Toshiba")
        (field (name "MPN_1") "TPH2R506PL,L1Q")
      )
      (libsource (lib "eagle-import") (part "TPH1R204PLSOP_ADVANCE_8"))
    )
    (comp (ref "Q5")
      (value "TPH1R204PLSOP_ADVANCE_8")
      (footprint "eagle-import:SOP_ADVANCE_8")
      (fields
        (field (name "MF") "Toshiba")
        (field (name "MPN") "TPH1R204PL")
        (field (name "MF_1") "Toshiba")
        (field (name "MPN_1") "TPH2R506PL,L1Q")
      )
      (libsource (lib "eagle-import") (part "TPH1R204PLSOP_ADVANCE_8"))
    )
    (comp (ref "Q6")
      (value "TPH1R204PLSOP_ADVANCE_8")
      (footprint "eagle-import:SOP_ADVANCE_8")
      (fields
        (field (name "MF") "Toshiba")
        (field (name "MPN") "TPH1R204PL")
        (field (name "MF_1") "Toshiba")
        (field (name "MPN_1") "TPH2R506PL,L1Q")
      )
      (libsource (lib "eagle-import") (part "TPH1R204PLSOP_ADVANCE_8"))
    )
    (comp (ref "R1")
      (value "560")
      (footprint "eagle-import:R0402")
      (fields (field (name "HOUSEPART") "1") (field (name "MPN") "MF-RES-0402-560"))
      (libsource (lib "eagle-import") (part "mfpassives_RESISTOR_0402"))
    )
    (comp (ref "R2")
      (value "560")
      (footprint "eagle-import:R0402")
      (fields (field (name "HOUSEPART") "1") (field (name "MPN") "MF-RES-0402-560"))
      (libsource (lib "eagle-import") (part "mfpassives_RESISTOR_0402"))
    )
    (comp (ref "R3")
      (value "2k")
      (footprint "eagle-import:R0402")
      (fields (field (name "HOUSEPART") "YES") (field (name "MPN") "MF-RES-0402-2K"))
      (libsource (lib "eagle-import") (part "mfpassives_RESISTOR_0402"))
    )
    (comp (ref "R4")
      (value "2k")
      (footprint "eagle-import:R0402")
      (fields (field (name "HOUSEPART") "YES") (field (name "MPN") "MF-RES-0402-2K"))
      (libsource (lib "eagle-import") (part "mfpassives_RESISTOR_0402"))
    )
    (comp (ref "R5")
      (value "100k 1%")
      (footprint "eagle-import:R0402")
      (fields (field (name "MF") "Yageo") (field (name "MPN") "RC0402FR-07100KL"))
      (libsource (lib "eagle-import") (part "mfpassives_RESISTOR_0402"))
    )
    (comp (ref "R6")
      (value "4.7k 1%")
      (footprint "eagle-import:R0402")
      (fields (field (name "MF") "Yageo") (field (name "MPN") "RC0402FR-074K7L"))
      (libsource (lib "eagle-import") (part "mfpassives_RESISTOR_0402"))
    )
    (comp (ref "R7")
      (value "10k 1%")
      (footprint "eagle-import:R0402")
      (fields (field (name "MF") "Yageo") (field (name "MPN") "RC0402FR-0710KL"))
      (libsource (lib "eagle-import") (part "mfpassives_RESISTOR_0402"))
    )
    (comp (ref "R8")
      (value "47k NTC")
      (footprint "eagle-import:R0402")
      (fields (field (name "MF") "Murata") (field (name "MPN") "NCP15WB473F03RC"))
      (libsource (lib "eagle-import") (part "mfpassives_RESISTOR_0402"))
    )
    (comp (ref "R9")
      (value "10k 1%")
      (footprint "eagle-import:R0402")
      (fields (field (name "MF") "Yageo") (field (name "MPN") "RC0402FR-0710KL"))
      (libsource (lib "eagle-import") (part "mfpassives_RESISTOR_0402"))
    )
    (comp (ref "R10")
      (value "DNP")
      (footprint "eagle-import:R0402")
      (fields (field (name "POPULATE") "0"))
      (libsource (lib "eagle-import") (part "mfpassives_RESISTOR_0402"))
    )
    (comp (ref "R13")
      (value "2k")
      (footprint "eagle-import:R0402")
      (fields (field (name "HOUSEPART") "YES") (field (name "MPN") "MF-RES-0402-2K"))
      (libsource (lib "eagle-import") (part "mfpassives_RESISTOR_0402"))
    )
    (comp (ref "R14")
      (value "2k")
      (footprint "eagle-import:R0402")
      (fields (field (name "HOUSEPART") "YES") (field (name "MPN") "MF-RES-0402-2K"))
      (libsource (lib "eagle-import") (part "mfpassives_RESISTOR_0402"))
    )
    (comp (ref "R15")
      (value "22")
      (footprint "eagle-import:R0402_NOBORDER")
      (fields (field (name "HOUSEPART") "1") (field (name "MPN") "MF-RES-0402-22"))
      (libsource (lib "eagle-import") (part "RESISTOR_0402_NOBORDER"))
    )
    (comp (ref "R16")
      (value "22")
      (footprint "eagle-import:R0402_NOBORDER")
      (fields (field (name "HOUSEPART") "1") (field (name "MPN") "MF-RES-0402-22"))
      (libsource (lib "eagle-import") (part "RESISTOR_0402_NOBORDER"))
    )
    (comp (ref "R17")
      (value "22")
      (footprint "eagle-import:R0402_NOBORDER")
      (fields (field (name "HOUSEPART") "1") (field (name "MPN") "MF-RES-0402-22"))
      (libsource (lib "eagle-import") (part "RESISTOR_0402_NOBORDER"))
    )
    (comp (ref "R22")
      (value "7.5")
      (footprint "eagle-import:R0402")
      (fields (field (name "HOUSEPART") "1") (field (name "MPN") "RC0402FR-077R5L"))
      (libsource (lib "eagle-import") (part "mfpassives_RESISTOR_0402"))
    )
    (comp (ref "R23")
      (value "7.5")
      (footprint "eagle-import:R0402")
      (fields (field (name "HOUSEPART") "1") (field (name "MPN") "RC0402FR-077R5L"))
      (libsource (lib "eagle-import") (part "mfpassives_RESISTOR_0402"))
    )
    (comp (ref "R24")
      (value "7.5")
      (footprint "eagle-import:R0402")
      (fields (field (name "HOUSEPART") "1") (field (name "MPN") "RC0402FR-077R5L"))
      (libsource (lib "eagle-import") (part "mfpassives_RESISTOR_0402"))
    )
    (comp (ref "R25")
      (value "7.5")
      (footprint "eagle-import:R0402")
      (fields (field (name "HOUSEPART") "1") (field (name "MPN") "RC0402FR-077R5L"))
      (libsource (lib "eagle-import") (part "mfpassives_RESISTOR_0402"))
    )
    (comp (ref "R26")
      (value "7.5")
      (footprint "eagle-import:R0402")
      (fields (field (name "HOUSEPART") "1") (field (name "MPN") "RC0402FR-077R5L"))
      (libsource (lib "eagle-import") (part "mfpassives_RESISTOR_0402"))
    )
    (comp (ref "R27")
      (value "7.5")
      (footprint "eagle-import:R0402")
      (fields (field (name "HOUSEPART") "1") (field (name "MPN") "RC0402FR-077R5L"))
      (libsource (lib "eagle-import") (part "mfpassives_RESISTOR_0402"))
    )
    (comp (ref "RA")
      (value "0.5mOhm 1% 2W")
      (footprint "eagle-import:M1206")
      (fields (field (name "MF") "Stackpole Electronics") (field (name "MPN") "HCS1206FTL500"))
      (libsource (lib "eagle-import") (part "R-US_M1206"))
    )
    (comp (ref "RB")
      (value "0.5mOhm 1% 2W")
      (footprint "eagle-import:M1206")
      (fields (field (name "MF") "Stackpole Electronics") (field (name "MPN") "HCS1206FTL500"))
      (libsource (lib "eagle-import") (part "R-US_M1206"))
    )
    (comp (ref "RC")
      (value "0.5mOhm 1% 2W")
      (footprint "eagle-import:M1206")
      (fields (field (name "MF") "Stackpole Electronics") (field (name "MPN") "HCS1206FTL500"))
      (libsource (lib "eagle-import") (part "R-US_M1206"))
    )
    (comp (ref "SH1")
      (value "SHORTT5")
      (footprint "eagle-import:SHORT_TOP-50")
      (libsource (lib "eagle-import") (part "SHORTT5"))
    )
    (comp (ref "SH2")
      (value "SHORTT5")
      (footprint "eagle-import:SHORT_TOP-50")
      (libsource (lib "eagle-import") (part "SHORTT5"))
    )
    (comp (ref "SH3")
      (value "SHORTT5")
      (footprint "eagle-import:SHORT_TOP-50")
      (libsource (lib "eagle-import") (part "SHORTT5"))
    )
    (comp (ref "SH4")
      (value "SHORTMEDIUM")
      (footprint "eagle-import:SHORT_TOP-MEDIUM")
      (libsource (lib "eagle-import") (part "SHORTMEDIUM"))
    )
    (comp (ref "SWD")
      (value "JST-ZH6")
      (footprint "eagle-import:JST_S6B-ZR-SM4A-TF(LF)(SN)")
      (fields (field (name "MF") "JST") (field (name "MPN") "S6B-ZR-SM4A-TF(LF)(SN)"))
      (libsource (lib "eagle-import") (part "JST-ZH6"))
    )
    (comp (ref "TEMP1")
      (value "PAD24AWG_PAD")
      (footprint "eagle-import:24AWG_PAD")
      (libsource (lib "eagle-import") (part "PAD24AWG_PAD"))
    )
    (comp (ref "TEMP2")
      (value "PAD24AWG_PAD")
      (footprint "eagle-import:24AWG_PAD")
      (libsource (lib "eagle-import") (part "PAD24AWG_PAD"))
    )
    (comp (ref "U1")
      (value "STM32G474CEU6")
      (footprint "eagle-import:QFN50P700X700X60-49N")
      (fields (field (name "MOUSER_PART_NUMBER") "511-STM32G474CEU6"))
      (libsource (lib "eagle-import") (part "STM32G474CEU6"))
    )
    (comp (ref "U2")
      (value "TCAN334G")
      (footprint "eagle-import:SOIC8")
      (fields (field (name "MF") "TI") (field (name "MPN") "TCAN337GDR"))
      (libsource (lib "eagle-import") (part "TCAN334G"))
    )
    (comp (ref "U3")
      (value "AS5147")
      (footprint "eagle-import:TSSOP14")
      (fields (field (name "MF") "AMS") (field (name "MPN") "AS5047P-ATSM"))
      (libsource (lib "eagle-import") (part "AS5147"))
    )
    (comp (ref "U4")
      (value "MAX15062AATA+T")
      (footprint "eagle-import:21-0487A_MXM")
      (fields (field (name "COPYRIGHT") "Copyright (C) 2018 Accelerated Designs. All rights reserved"))
      (libsource (lib "eagle-import") (part "MAX15062AATA+T"))
    )
    (comp (ref "U5")
      (value "DRV8353S")
      (footprint "eagle-import:WQFN-40")
      (fields (field (name "MF") "TI") (field (name "MPN") "DRV8353FSRTAR"))
      (libsource (lib "eagle-import") (part "DRV8353S"))
    )
    (comp (ref "U6")
      (value "TCAN334GSOT23-8-NOPASTE")
      (footprint "eagle-import:SOT23-8-NOPASTE")
      (fields (field (name "MF") "TI") (field (name "MPN") "TCAN334GDCNT"))
      (libsource (lib "eagle-import") (part "TCAN334GSOT23-8-NOPASTE"))
    )
  )
  (nets
    (net (code "1") (name "+3V3") (class "Default")
      (node (ref "ABS") (pin "1") (pinfunction "1_1") (pintype "passive"))
      (node (ref "C1") (pin "P$1") (pinfunction "P$1_P$1") (pintype "passive"))
      (node (ref "C10") (pin "P$1") (pinfunction "P$1_P$1") (pintype "passive"))
      (node (ref "C11") (pin "P$1") (pinfunction "P$1_P$1") (pintype "passive"))
      (node (ref "C12") (pin "P$1") (pinfunction "P$1_P$1") (pintype "passive"))
      (node (ref "C18") (pin "P$2") (pinfunction "P$2_P$2") (pintype "passive"))
      (node (ref "C2") (pin "P$1") (pinfunction "P$1_P$1") (pintype "passive"))
      (node (ref "C21") (pin "P$1") (pinfunction "P$1_P$1") (pintype "passive"))
      (node (ref "C4") (pin "P$1") (pinfunction "P$1_P$1") (pintype "passive"))
      (node (ref "C5") (pin "P$1") (pinfunction "P$1_P$1") (pintype "passive"))
      (node (ref "C56") (pin "P$1") (pinfunction "P$1_P$1") (pintype "passive"))
      (node (ref "C6") (pin "P$1") (pinfunction "P$1_P$1") (pintype "passive"))
      (node (ref "C7") (pin "P$2") (pinfunction "P$2_P$2") (pintype "passive"))
      (node (ref "C8") (pin "P$1") (pinfunction "P$1_P$1") (pintype "passive"))
      (node (ref "C9") (pin "P$1") (pinfunction "P$1_P$1") (pintype "passive"))
      (node (ref "D33") (pin "P$1") (pinfunction "P$1_P$1") (pintype "bidirectional"))
      (node (ref "ENC") (pin "1") (pinfunction "1_1") (pintype "passive"))
      (node (ref "L1") (pin "1") (pinfunction "1_1") (pintype "passive"))
      (node (ref "R1") (pin "P$1") (pinfunction "P$1_P$1") (pintype "passive"))
      (node (ref "R13") (pin "P$1") (pinfunction "P$1_P$1") (pintype "passive"))
      (node (ref "R14") (pin "P$1") (pinfunction "P$1_P$1") (pintype "passive"))
      (node (ref "R2") (pin "P$1") (pinfunction "P$1_P$1") (pintype "passive"))
      (node (ref "R3") (pin "P$1") (pinfunction "P$1_P$1") (pintype "passive"))
      (node (ref "R4") (pin "P$1") (pinfunction "P$1_P$1") (pintype "passive"))
      (node (ref "R8") (pin "P$1") (pinfunction "P$1_P$1") (pintype "passive"))
      (node (ref "SWD") (pin "6") (pinfunction "6_6") (pintype "passive"))
      (node (ref "TEMP1") (pin "P$1") (pinfunction "P$1_P$1") (pintype "bidirectional"))
      (node (ref "U1") (pin "1") (pinfunction "VBAT_1") (pintype "bidirectional"))
      (node (ref "U1") (pin "20") (pinfunction "VREF+_20") (pintype "bidirectional"))
      (node (ref "U1") (pin "21") (pinfunction "VDDA_21") (pintype "bidirectional"))
      (node (ref "U1") (pin "23") (pinfunction "VDD_1_23") (pintype "bidirectional"))
      (node (ref "U1") (pin "35") (pinfunction "VDD_2_35") (pintype "bidirectional"))
      (node (ref "U1") (pin "48") (pinfunction "VDD_3_48") (pintype "bidirectional"))
      (node (ref "U2") (pin "3") (pinfunction "VCC_3") (pintype "power_in"))
      (node (ref "U3") (pin "12") (pinfunction "VDD3V_12") (pintype "bidirectional"))
      (node (ref "U4") (pin "4") (pinfunction "FB/VOUT_4") (pintype "bidirectional"))
      (node (ref "U5") (pin "24") (pinfunction "VREF_24") (pintype "bidirectional"))
      (node (ref "U6") (pin "3") (pinfunction "VCC_3") (pintype "power_in"))
    )
    (net (code "2") (name "/AS5047_A") (class "Default")
      (node (ref "U1") (pin "43") (pinfunction "PB5_43") (pintype "bidirectional"))
      (node (ref "U3") (pin "7") (pinfunction "A_7") (pintype "bidirectional"))
    )
    (net (code "3") (name "/AS5047_B") (class "Default")
      (node (ref "U1") (pin "42") (pinfunction "PB4_42") (pintype "bidirectional"))
      (node (ref "U3") (pin "6") (pinfunction "B_6") (pintype "bidirectional"))
    )
    (net (code "4") (name "/AS5047_CS") (class "Default")
      (node (ref "U1") (pin "24") (pinfunction "PB11_24") (pintype "bidirectional"))
      (node (ref "U3") (pin "1") (pinfunction "CS/_1") (pintype "bidirectional"))
    )
    (net (code "5") (name "/AS5047_MISO") (class "Default")
      (node (ref "ENC") (pin "5") (pinfunction "5_5") (pintype "passive"))
      (node (ref "U1") (pin "27") (pinfunction "PB14_27") (pintype "bidirectional"))
      (node (ref "U3") (pin "3") (pinfunction "MISO_3") (pintype "bidirectional"))
    )
    (net (code "6") (name "/AS5047_MOSI") (class "Default")
      (node (ref "ENC") (pin "6") (pinfunction "6_6") (pintype "passive"))
      (node (ref "U1") (pin "28") (pinfunction "PB15_28") (pintype "bidirectional"))
      (node (ref "U3") (pin "4") (pinfunction "MOSI_4") (pintype "bidirectional"))
    )
    (net (code "7") (name "/AS5047_SCK") (class "Default")
      (node (ref "ENC") (pin "4") (pinfunction "4_4") (pintype "passive"))
      (node (ref "U1") (pin "26") (pinfunction "PB13_26") (pintype "bidirectional"))
      (node (ref "U3") (pin "2") (pinfunction "CLK_2") (pintype "bidirectional"))
    )
    (net (code "8") (name "/CAN2_N") (class "Default")
      (node (ref "L2") (pin "P$2") (pinfunction "2_P$2") (pintype "passive"))
      (node (ref "U2") (pin "6") (pinfunction "CANL_6") (pintype "bidirectional"))
      (node (ref "U6") (pin "6") (pinfunction "CANL_6") (pintype "bidirectional"))
    )
    (net (code "9") (name "/CAN2_P") (class "Default")
      (node (ref "L3") (pin "P$2") (pinfunction "2_P$2") (pintype "passive"))
      (node (ref "U2") (pin "7") (pinfunction "CANH_7") (pintype "bidirectional"))
      (node (ref "U6") (pin "7") (pinfunction "CANH_7") (pintype "bidirectional"))
    )
    (net (code "10") (name "/CAN_N") (class "Default")
      (node (ref "CAN1") (pin "2") (pinfunction "2_2") (pintype "passive"))
      (node (ref "CAN2") (pin "2") (pinfunction "2_2") (pintype "passive"))
      (node (ref "D4") (pin "2") (pinfunction "2_2") (pintype "bidirectional"))
      (node (ref "L2") (pin "P$1") (pinfunction "1_P$1") (pintype "passive"))
    )
    (net (code "11") (name "/CAN_P") (class "Default")
      (node (ref "CAN1") (pin "1") (pinfunction "1_1") (pintype "passive"))
      (node (ref "CAN2") (pin "1") (pinfunction "1_1") (pintype "passive"))
      (node (ref "D4") (pin "1") (pinfunction "1_1") (pintype "bidirectional"))
      (node (ref "L3") (pin "P$1") (pinfunction "1_P$1") (pintype "passive"))
    )
    (net (code "12") (name "/CAN_RX") (class "Default")
      (node (ref "U1") (pin "33") (pinfunction "PA11_33") (pintype "bidirectional"))
      (node (ref "U2") (pin "4") (pinfunction "RXD_4") (pintype "output"))
      (node (ref "U6") (pin "4") (pinfunction "RXD_4") (pintype "output"))
    )
    (net (code "13") (name "/CAN_TX") (class "Default")
      (node (ref "U1") (pin "34") (pinfunction "PA12_34") (pintype "bidirectional"))
      (node (ref "U2") (pin "1") (pinfunction "TXD_1") (pintype "input"))
      (node (ref "U6") (pin "1") (pinfunction "TXD_1") (pintype "input"))
    )
    (net (code "14") (name "/CUR1") (class "Default")
      (node (ref "R15") (pin "P$1") (pinfunction "P$1_P$1") (pintype "passive"))
      (node (ref "U5") (pin "23") (pinfunction "SOA_23") (pintype "bidirectional"))
    )
    (net (code "15") (name "/CUR2") (class "Default")
      (node (ref "R16") (pin "P$1") (pinfunction "P$1_P$1") (pintype "passive"))
      (node (ref "U5") (pin "22") (pinfunction "SOB_22") (pintype "bidirectional"))
    )
    (net (code "16") (name "/CUR3") (class "Default")
      (node (ref "R17") (pin "P$1") (pinfunction "P$1_P$1") (pintype "passive"))
      (node (ref "U5") (pin "21") (pinfunction "SOC_21") (pintype "bidirectional"))
    )
    (net (code "17") (name "/DAC") (class "Default")
      (node (ref "DAC") (pin "P$1") (pinfunction "P$1_P$1") (pintype "bidirectional"))
      (node (ref "U1") (pin "12") (pinfunction "PA4_12") (pintype "bidirectional"))
    )
    (net (code "18") (name "/DEBUG1") (class "Default")
      (node (ref "DBG1") (pin "P$1") (pinfunction "P$1_P$1") (pintype "bidirectional"))
      (node (ref "U1") (pin "3") (pinfunction "PC14-OSC32_IN_3") (pintype "bidirectional"))
    )
    (net (code "19") (name "/DEBUG2") (class "Default")
      (node (ref "DBG2") (pin "P$1") (pinfunction "P$1_P$1") (pintype "bidirectional"))
      (node (ref "U1") (pin "4") (pinfunction "PC15-OSC32_OUT_4") (pintype "bidirectional"))
    )
    (net (code "20") (name "/DEBUG_RX") (class "Default")
      (node (ref "DTR") (pin "P$1") (pinfunction "P$1_P$1") (pintype "bidirectional"))
      (node (ref "U1") (pin "40") (pinfunction "PC11_40") (pintype "bidirectional"))
    )
    (net (code "21") (name "/DEBUG_TX") (class "Default")
      (node (ref "DTX") (pin "P$1") (pinfunction "P$1_P$1") (pintype "bidirectional"))
      (node (ref "U1") (pin "39") (pinfunction "PC10_39") (pintype "bidirectional"))
    )
    (net (code "22") (name "/DRV8323_CS") (class "Default")
      (node (ref "DRV_CS") (pin "P$1") (pinfunction "P$1_P$1") (pintype "bidirectional"))
      (node (ref "U1") (pin "16") (pinfunction "PC4_16") (pintype "bidirectional"))
      (node (ref "U5") (pin "30") (pinfunction "CS_30") (pintype "bidirectional"))
    )
    (net (code "23") (name "/DRV8323_MISO") (class "Default")
      (node (ref "DRV_MISO") (pin "P$1") (pinfunction "P$1_P$1") (pintype "bidirectional"))
      (node (ref "R13") (pin "P$2") (pinfunction "P$2_P$2") (pintype "passive"))
      (node (ref "U1") (pin "14") (pinfunction "PA6_14") (pintype "bidirectional"))
      (node (ref "U5") (pin "27") (pinfunction "MISO_27") (pintype "bidirectional"))
    )
    (net (code "24") (name "/DRV8323_MOSI") (class "Default")
      (node (ref "DRV_MOSI") (pin "P$1") (pinfunction "P$1_P$1") (pintype "bidirectional"))
      (node (ref "U1") (pin "15") (pinfunction "PA7_15") (pintype "bidirectional"))
      (node (ref "U5") (pin "28") (pinfunction "MOSI_28") (pintype "bidirectional"))
    )
    (net (code "25") (name "/DRV8323_SCLK") (class "Default")
      (node (ref "DRV_SCK") (pin "P$1") (pinfunction "P$1_P$1") (pintype "bidirectional"))
      (node (ref "U1") (pin "13") (pinfunction "PA5_13") (pintype "bidirectional"))
      (node (ref "U5") (pin "29") (pinfunction "SCLK_29") (pintype "bidirectional"))
    )
    (net (code "26") (name "/FCUR1") (class "Default")
      (node (ref "C58") (pin "P$1") (pinfunction "P$1_P$1") (pintype "passive"))
      (node (ref "R15") (pin "P$2") (pinfunction "P$2_P$2") (pintype "passive"))
      (node (ref "U1") (pin "17") (pinfunction "PB0_17") (pintype "bidirectional"))
    )
    (net (code "27") (name "/FCUR2") (class "Default")
      (node (ref "C59") (pin "P$1") (pinfunction "P$1_P$1") (pintype "passive"))
      (node (ref "R16") (pin "P$2") (pinfunction "P$2_P$2") (pintype "passive"))
      (node (ref "U1") (pin "18") (pinfunction "PB1_18") (pintype "bidirectional"))
    )
    (net (code "28") (name "/FCUR3") (class "Default")
      (node (ref "C60") (pin "P$1") (pinfunction "P$1_P$1") (pintype "passive"))
      (node (ref "R17") (pin "P$2") (pinfunction "P$2_P$2") (pintype "passive"))
      (node (ref "U1") (pin "19") (pinfunction "PB2_19") (pintype "bidirectional"))
    )
    (net (code "29") (name "/GHA") (class "Default")
      (node (ref "D10") (pin "1") (pinfunction "K_1") (pintype "bidirectional"))
      (node (ref "R22") (pin "P$1") (pinfunction "P$1_P$1") (pintype "passive"))
      (node (ref "U5") (pin "6") (pinfunction "GHA_6") (pintype "bidirectional"))
    )
    (net (code "30") (name "/GHA_D") (class "Default")
      (node (ref "D10") (pin "2") (pinfunction "A_2") (pintype "bidirectional"))
      (node (ref "Q1") (pin "4") (pinfunction "G_4") (pintype "passive"))
      (node (ref "R22") (pin "P$2") (pinfunction "P$2_P$2") (pintype "passive"))
    )
    (net (code "31") (name "/GHB") (class "Default")
      (node (ref "D11") (pin "1") (pinfunction "K_1") (pintype "bidirectional"))
      (node (ref "R24") (pin "P$1") (pinfunction "P$1_P$1") (pintype "passive"))
      (node (ref "U5") (pin "15") (pinfunction "GHB_15") (pintype "bidirectional"))
    )
    (net (code "32") (name "/GHB_D") (class "Default")
      (node (ref "D11") (pin "2") (pinfunction "A_2") (pintype "bidirectional"))
      (node (ref "Q3") (pin "4") (pinfunction "G_4") (pintype "passive"))
      (node (ref "R24") (pin "P$2") (pinfunction "P$2_P$2") (pintype "passive"))
    )
    (net (code "33") (name "/GHC") (class "Default")
      (node (ref "D12") (pin "1") (pinfunction "K_1") (pintype "bidirectional"))
      (node (ref "R26") (pin "P$1") (pinfunction "P$1_P$1") (pintype "passive"))
      (node (ref "U5") (pin "16") (pinfunction "GHC_16") (pintype "bidirectional"))
    )
    (net (code "34") (name "/GHC_D") (class "Default")
      (node (ref "D12") (pin "2") (pinfunction "A_2") (pintype "bidirectional"))
      (node (ref "Q5") (pin "4") (pinfunction "G_4") (pintype "passive"))
      (node (ref "R26") (pin "P$2") (pinfunction "P$2_P$2") (pintype "passive"))
    )
    (net (code "35") (name "/GLA") (class "Default")
      (node (ref "D7") (pin "1") (pinfunction "K_1") (pintype "bidirectional"))
      (node (ref "R23") (pin "P$1") (pinfunction "P$1_P$1") (pintype "passive"))
      (node (ref "U5") (pin "8") (pinfunction "GLA_8") (pintype "bidirectional"))
    )
    (net (code "36") (name "/GLA_D") (class "Default")
      (node (ref "D1") (pin "1") (pinfunction "K_1") (pintype "bidirectional"))
      (node (ref "D7") (pin "2") (pinfunction "A_2") (pintype "bidirectional"))
      (node (ref "Q2") (pin "4") (pinfunction "G_4") (pintype "passive"))
      (node (ref "R23") (pin "P$2") (pinfunction "P$2_P$2") (pintype "passive"))
    )
    (net (code "37") (name "/GLB") (class "Default")
      (node (ref "D8") (pin "1") (pinfunction "K_1") (pintype "bidirectional"))
      (node (ref "R25") (pin "P$1") (pinfunction "P$1_P$1") (pintype "passive"))
      (node (ref "U5") (pin "13") (pinfunction "GLB_13") (pintype "bidirectional"))
    )
    (net (code "38") (name "/GLB_D") (class "Default")
      (node (ref "D5") (pin "1") (pinfunction "K_1") (pintype "bidirectional"))
      (node (ref "D8") (pin "2") (pinfunction "A_2") (pintype "bidirectional"))
      (node (ref "Q4") (pin "4") (pinfunction "G_4") (pintype "passive"))
      (node (ref "R25") (pin "P$2") (pinfunction "P$2_P$2") (pintype "passive"))
    )
    (net (code "39") (name "/GLC") (class "Default")
      (node (ref "D9") (pin "1") (pinfunction "K_1") (pintype "bidirectional"))
      (node (ref "R27") (pin "P$1") (pinfunction "P$1_P$1") (pintype "passive"))
      (node (ref "U5") (pin "18") (pinfunction "GLC_18") (pintype "bidirectional"))
    )
    (net (code "40") (name "/GLC_D") (class "Default")
      (node (ref "D6") (pin "1") (pinfunction "K_1") (pintype "bidirectional"))
      (node (ref "D9") (pin "2") (pinfunction "A_2") (pintype "bidirectional"))
      (node (ref "Q6") (pin "4") (pinfunction "G_4") (pintype "passive"))
      (node (ref "R27") (pin "P$2") (pinfunction "P$2_P$2") (pintype "passive"))
    )
    (net (code "41") (name "/I2C_ABS_SCL") (class "Default")
      (node (ref "ABS") (pin "2") (pinfunction "2_2") (pintype "passive"))
      (node (ref "R4") (pin "P$2") (pinfunction "P$2_P$2") (pintype "passive"))
      (node (ref "U1") (pin "46") (pinfunction "PB8-BOOT0_46") (pintype "bidirectional"))
    )
    (net (code "42") (name "/I2C_ABS_SDA") (class "Default")
      (node (ref "ABS") (pin "3") (pinfunction "3_3") (pintype "passive"))
      (node (ref "R3") (pin "P$2") (pinfunction "P$2_P$2") (pintype "passive"))
      (node (ref "U1") (pin "47") (pinfunction "PB9_47") (pintype "bidirectional"))
    )
    (net (code "43") (name "/LED1") (class "Default")
      (node (ref "D3") (pin "CATHODE") (pinfunction "CATHODE_CATHODE") (pintype "power_in"))
      (node (ref "U1") (pin "5") (pinfunction "PF0-OSC_IN_5") (pintype "bidirectional"))
    )
    (net (code "44") (name "/LED2") (class "Default")
      (node (ref "D2") (pin "CATHODE") (pinfunction "CATHODE_CATHODE") (pintype "power_in"))
      (node (ref "U1") (pin "6") (pinfunction "PF1-OSC_OUT_6") (pintype "bidirectional"))
    )
    (net (code "45") (name "/MOTOR1") (class "Default")
      (node (ref "MOT1") (pin "P$1") (pinfunction "P$1_P$1") (pintype "bidirectional"))
      (node (ref "U1") (pin "8") (pinfunction "PA0_8") (pintype "bidirectional"))
      (node (ref "U5") (pin "32") (pinfunction "INHA_32") (pintype "bidirectional"))
    )
    (net (code "46") (name "/MOTOR2") (class "Default")
      (node (ref "MOT2") (pin "P$1") (pinfunction "P$1_P$1") (pintype "bidirectional"))
      (node (ref "U1") (pin "9") (pinfunction "PA1_9") (pintype "bidirectional"))
      (node (ref "U5") (pin "34") (pinfunction "INHB_34") (pintype "bidirectional"))
    )
    (net (code "47") (name "/MOTOR3") (class "Default")
      (node (ref "MOT3") (pin "P$1") (pinfunction "P$1_P$1") (pintype "bidirectional"))
      (node (ref "U1") (pin "10") (pinfunction "PA2_10") (pintype "bidirectional"))
      (node (ref "U5") (pin "36") (pinfunction "INHC_36") (pintype "bidirectional"))
    )
    (net (code "48") (name "/MOTOR_ENABLE") (class "Default")
      (node (ref "U1") (pin "11") (pinfunction "PA3_11") (pintype "bidirectional"))
      (node (ref "U5") (pin "31") (pinfunction "ENABLE_31") (pintype "bidirectional"))
    )
    (net (code "49") (name "/MOTOR_FAULT") (class "Default")
      (node (ref "R14") (pin "P$2") (pinfunction "P$2_P$2") (pintype "passive"))
      (node (ref "U1") (pin "44") (pinfunction "PB6_44") (pintype "bidirectional"))
      (node (ref "U5") (pin "26") (pinfunction "FAULT_26") (pintype "bidirectional"))
    )
    (net (code "50") (name "/MOTOR_HIZ") (class "Default")
      (node (ref "U1") (pin "45") (pinfunction "PB7_45") (pintype "bidirectional"))
      (node (ref "U5") (pin "33") (pinfunction "INLA_33") (pintype "bidirectional"))
      (node (ref "U5") (pin "35") (pinfunction "INLB_35") (pintype "bidirectional"))
      (node (ref "U5") (pin "37") (pinfunction "INLC_37") (pintype "bidirectional"))
    )
    (net (code "51") (name "/NRST") (class "Default")
      (node (ref "C3") (pin "P$1") (pinfunction "P$1_P$1") (pintype "passive"))
      (node (ref "SWD") (pin "2") (pinfunction "2_2") (pintype "passive"))
      (node (ref "U1") (pin "7") (pinfunction "PG10-NRST_7") (pintype "bidirectional"))
    )
    (net (code "52") (name "/SECONDARY_ENC_CS") (class "Default")
      (node (ref "ENC") (pin "2") (pinfunction "2_2") (pintype "passive"))
      (node (ref "U1") (pin "2") (pinfunction "PC13_2") (pintype "bidirectional"))
    )
    (net (code "53") (name "/SHA") (class "Default")
      (node (ref "A") (pin "1") (pinfunction "P$1_1") (pintype "bidirectional"))
      (node (ref "DA") (pin "P$1") (pinfunction "P$1_P$1") (pintype "bidirectional"))
      (node (ref "Q1") (pin "1") (pinfunction "S_1") (pintype "passive"))
      (node (ref "Q1") (pin "2") (pinfunction "S_2") (pintype "passive"))
      (node (ref "Q1") (pin "3") (pinfunction "S_3") (pintype "passive"))
      (node (ref "Q2") (pin "5") (pinfunction "D_5") (pintype "passive"))
      (node (ref "Q2") (pin "6") (pinfunction "D_6") (pintype "passive"))
      (node (ref "Q2") (pin "7") (pinfunction "D_7") (pintype "passive"))
      (node (ref "Q2") (pin "8") (pinfunction "D_8") (pintype "passive"))
      (node (ref "Q2") (pin "PAD") (pinfunction "D_PAD") (pintype "passive"))
      (node (ref "U5") (pin "7") (pinfunction "SHA_7") (pintype "bidirectional"))
    )
    (net (code "54") (name "/SHB") (class "Default")
      (node (ref "B") (pin "1") (pinfunction "P$1_1") (pintype "bidirectional"))
      (node (ref "DB") (pin "P$1") (pinfunction "P$1_P$1") (pintype "bidirectional"))
      (node (ref "Q3") (pin "1") (pinfunction "S_1") (pintype "passive"))
      (node (ref "Q3") (pin "2") (pinfunction "S_2") (pintype "passive"))
      (node (ref "Q3") (pin "3") (pinfunction "S_3") (pintype "passive"))
      (node (ref "Q4") (pin "5") (pinfunction "D_5") (pintype "passive"))
      (node (ref "Q4") (pin "6") (pinfunction "D_6") (pintype "passive"))
      (node (ref "Q4") (pin "7") (pinfunction "D_7") (pintype "passive"))
      (node (ref "Q4") (pin "8") (pinfunction "D_8") (pintype "passive"))
      (node (ref "Q4") (pin "PAD") (pinfunction "D_PAD") (pintype "passive"))
      (node (ref "U5") (pin "14") (pinfunction "SHB_14") (pintype "bidirectional"))
    )
    (net (code "55") (name "/SHC") (class "Default")
      (node (ref "C") (pin "1") (pinfunction "P$1_1") (pintype "bidirectional"))
      (node (ref "DC") (pin "P$1") (pinfunction "P$1_P$1") (pintype "bidirectional"))
      (node (ref "Q5") (pin "1") (pinfunction "S_1") (pintype "passive"))
      (node (ref "Q5") (pin "2") (pinfunction "S_2") (pintype "passive"))
      (node (ref "Q5") (pin "3") (pinfunction "S_3") (pintype "passive"))
      (node (ref "Q6") (pin "5") (pinfunction "D_5") (pintype "passive"))
      (node (ref "Q6") (pin "6") (pinfunction "D_6") (pintype "passive"))
      (node (ref "Q6") (pin "7") (pinfunction "D_7") (pintype "passive"))
      (node (ref "Q6") (pin "8") (pinfunction "D_8") (pintype "passive"))
      (node (ref "Q6") (pin "PAD") (pinfunction "D_PAD") (pintype "passive"))
      (node (ref "U5") (pin "17") (pinfunction "SHC_17") (pintype "bidirectional"))
    )
    (net (code "56") (name "/SWCLK") (class "Default")
      (node (ref "SWD") (pin "5") (pinfunction "5_5") (pintype "passive"))
      (node (ref "U1") (pin "37") (pinfunction "PA14_37") (pintype "bidirectional"))
    )
    (net (code "57") (name "/SWDIO") (class "Default")
      (node (ref "SWD") (pin "3") (pinfunction "3_3") (pintype "passive"))
      (node (ref "U1") (pin "36") (pinfunction "PA13_36") (pintype "bidirectional"))
    )
    (net (code "58") (name "/SXA_N") (class "Default")
      (node (ref "SH1") (pin "1") (pinfunction "P$1_1") (pintype "bidirectional"))
      (node (ref "U5") (pin "10") (pinfunction "SNA_10") (pintype "bidirectional"))
    )
    (net (code "59") (name "/SXA_P") (class "Default")
      (node (ref "C61") (pin "P$2") (pinfunction "P$2_P$2") (pintype "passive"))
      (node (ref "Q2") (pin "1") (pinfunction "S_1") (pintype "passive"))
      (node (ref "Q2") (pin "2") (pinfunction "S_2") (pintype "passive"))
      (node (ref "Q2") (pin "3") (pinfunction "S_3") (pintype "passive"))
      (node (ref "RA") (pin "2") (pinfunction "2_2") (pintype "passive"))
      (node (ref "U5") (pin "9") (pinfunction "SPA_9") (pintype "bidirectional"))
    )
    (net (code "60") (name "/SXB_N") (class "Default")
      (node (ref "SH2") (pin "1") (pinfunction "P$1_1") (pintype "bidirectional"))
      (node (ref "U5") (pin "11") (pinfunction "SNB_11") (pintype "bidirectional"))
    )
    (net (code "61") (name "/SXB_P") (class "Default")
      (node (ref "C62") (pin "P$2") (pinfunction "P$2_P$2") (pintype "passive"))
      (node (ref "Q4") (pin "1") (pinfunction "S_1") (pintype "passive"))
      (node (ref "Q4") (pin "2") (pinfunction "S_2") (pintype "passive"))
      (node (ref "Q4") (pin "3") (pinfunction "S_3") (pintype "passive"))
      (node (ref "RB") (pin "2") (pinfunction "2_2") (pintype "passive"))
      (node (ref "U5") (pin "12") (pinfunction "SPB_12") (pintype "bidirectional"))
    )
    (net (code "62") (name "/SXC_N") (class "Default")
      (node (ref "SH3") (pin "1") (pinfunction "P$1_1") (pintype "bidirectional"))
      (node (ref "U5") (pin "20") (pinfunction "SNC_20") (pintype "bidirectional"))
    )
    (net (code "63") (name "/SXC_P") (class "Default")
      (node (ref "C63") (pin "P$2") (pinfunction "P$2_P$2") (pintype "passive"))
      (node (ref "Q6") (pin "1") (pinfunction "S_1") (pintype "passive"))
      (node (ref "Q6") (pin "2") (pinfunction "S_2") (pintype "passive"))
      (node (ref "Q6") (pin "3") (pinfunction "S_3") (pintype "passive"))
      (node (ref "RC") (pin "2") (pinfunction "2_2") (pintype "passive"))
      (node (ref "U5") (pin "19") (pinfunction "SPC_19") (pintype "bidirectional"))
    )
    (net (code "64") (name "/VBAT_SENSE") (class "Default")
      (node (ref "C57") (pin "P$1") (pinfunction "P$1_P$1") (pintype "passive"))
      (node (ref "R5") (pin "P$1") (pinfunction "P$1_P$1") (pintype "passive"))
      (node (ref "R6") (pin "P$2") (pinfunction "P$2_P$2") (pintype "passive"))
      (node (ref "U1") (pin "25") (pinfunction "PB12_25") (pintype "bidirectional"))
    )
    (net (code "65") (name "/VSW") (class "Default")
      (node (ref "L1") (pin "2") (pinfunction "2_2") (pintype "passive"))
      (node (ref "U4") (pin "8") (pinfunction "LX_8") (pintype "passive"))
    )
    (net (code "66") (name "/VTEMP_FET") (class "Default")
      (node (ref "C13") (pin "P$1") (pinfunction "P$1_P$1") (pintype "passive"))
      (node (ref "R8") (pin "P$2") (pinfunction "P$2_P$2") (pintype "passive"))
      (node (ref "R9") (pin "P$1") (pinfunction "P$1_P$1") (pintype "passive"))
      (node (ref "U1") (pin "31") (pinfunction "PA9_31") (pintype "bidirectional"))
    )
    (net (code "67") (name "/VTEMP_MOT") (class "Default")
      (node (ref "R7") (pin "P$1") (pinfunction "P$1_P$1") (pintype "passive"))
      (node (ref "TEMP2") (pin "P$1") (pinfunction "P$1_P$1") (pintype "bidirectional"))
      (node (ref "U1") (pin "30") (pinfunction "PA8_30") (pintype "bidirectional"))
    )
    (net (code "68") (name "GND") (class "Default")
      (node (ref "ABS") (pin "4") (pinfunction "4_4") (pintype "passive"))
      (node (ref "C1") (pin "P$2") (pinfunction "P$2_P$2") (pintype "passive"))
      (node (ref "C10") (pin "P$2") (pinfunction "P$2_P$2") (pintype "passive"))
      (node (ref "C11") (pin "P$2") (pinfunction "P$2_P$2") (pintype "passive"))
      (node (ref "C12") (pin "P$2") (pinfunction "P$2_P$2") (pintype "passive"))
      (node (ref "C13") (pin "P$2") (pinfunction "P$2_P$2") (pintype "passive"))
      (node (ref "C18") (pin "P$1") (pinfunction "P$1_P$1") (pintype "passive"))
      (node (ref "C2") (pin "P$2") (pinfunction "P$2_P$2") (pintype "passive"))
      (node (ref "C20") (pin "P$2") (pinfunction "P$2_P$2") (pintype "passive"))
      (node (ref "C21") (pin "P$2") (pinfunction "P$2_P$2") (pintype "passive"))
      (node (ref "C3") (pin "P$2") (pinfunction "P$2_P$2") (pintype "passive"))
      (node (ref "C4") (pin "P$2") (pinfunction "P$2_P$2") (pintype "passive"))
      (node (ref "C5") (pin "P$2") (pinfunction "P$2_P$2") (pintype "passive"))
      (node (ref "C56") (pin "P$2") (pinfunction "P$2_P$2") (pintype "passive"))
      (node (ref "C57") (pin "P$2") (pinfunction "P$2_P$2") (pintype "passive"))
      (node (ref "C58") (pin "P$2") (pinfunction "P$2_P$2") (pintype "passive"))
      (node (ref "C59") (pin "P$2") (pinfunction "P$2_P$2") (pintype "passive"))
      (node (ref "C6") (pin "P$2") (pinfunction "P$2_P$2") (pintype "passive"))
      (node (ref "C60") (pin "P$2") (pinfunction "P$2_P$2") (pintype "passive"))
      (node (ref "C7") (pin "P$1") (pinfunction "P$1_P$1") (pintype "passive"))
      (node (ref "C8") (pin "P$2") (pinfunction "P$2_P$2") (pintype "passive"))
      (node (ref "C9") (pin "P$2") (pinfunction "P$2_P$2") (pintype "passive"))
      (node (ref "CAN1") (pin "3") (pinfunction "3_3") (pintype "passive"))
      (node (ref "CAN2") (pin "3") (pinfunction "3_3") (pintype "passive"))
      (node (ref "D4") (pin "3") (pinfunction "3_3") (pintype "bidirectional"))
      (node (ref "DG1") (pin "P$1") (pinfunction "P$1_P$1") (pintype "bidirectional"))
      (node (ref "DG2") (pin "P$1") (pinfunction "P$1_P$1") (pintype "bidirectional"))
      (node (ref "ENC") (pin "3") (pinfunction "3_3") (pintype "passive"))
      (node (ref "R6") (pin "P$1") (pinfunction "P$1_P$1") (pintype "passive"))
      (node (ref "R7") (pin "P$2") (pinfunction "P$2_P$2") (pintype "passive"))
      (node (ref "R9") (pin "P$2") (pinfunction "P$2_P$2") (pintype "passive"))
      (node (ref "SH4") (pin "2") (pinfunction "P$2_2") (pintype "bidirectional"))
      (node (ref "SWD") (pin "4") (pinfunction "4_4") (pintype "passive"))
      (node (ref "U1") (pin "32") (pinfunction "PA10_32") (pintype "bidirectional"))
      (node (ref "U1") (pin "49") (pinfunction "THERMALPAD_49") (pintype "bidirectional"))
      (node (ref "U2") (pin "2") (pinfunction "GND_2") (pintype "power_in"))
      (node (ref "U2") (pin "5") (pinfunction "SHDN_5") (pintype "input"))
      (node (ref "U2") (pin "8") (pinfunction "STB_8") (pintype "input"))
      (node (ref "U3") (pin "13") (pinfunction "GND_13") (pintype "bidirectional"))
      (node (ref "U3") (pin "5") (pinfunction "TEST_5") (pintype "bidirectional"))
      (node (ref "U4") (pin "7") (pinfunction "GND_7") (pintype "power_in"))
      (node (ref "U5") (pin "25") (pinfunction "AGND_25") (pintype "bidirectional"))
      (node (ref "U6") (pin "2") (pinfunction "GND_2") (pintype "power_in"))
      (node (ref "U6") (pin "5") (pinfunction "SHDN_5") (pintype "input"))
      (node (ref "U6") (pin "8") (pinfunction "STB_8") (pintype "input"))
    )
    (net (code "69") (name "Net-(C55-PadP$1)") (class "Default")
      (node (ref "C55") (pin "P$1") (pinfunction "P$1_P$1") (pintype "passive"))
      (node (ref "M3") (pin "P$1") (pinfunction "P$1_P$1") (pintype "bidirectional"))
      (node (ref "R10") (pin "P$1") (pinfunction "P$1_P$1") (pintype "passive"))
    )
    (net (code "70") (name "Net-(D2-PadANODE)") (class "Default")
      (node (ref "D2") (pin "ANODE") (pinfunction "ANODE_ANODE") (pintype "power_in"))
      (node (ref "R2") (pin "P$2") (pinfunction "P$2_P$2") (pintype "passive"))
    )
    (net (code "71") (name "Net-(D3-PadANODE)") (class "Default")
      (node (ref "D3") (pin "ANODE") (pinfunction "ANODE_ANODE") (pintype "power_in"))
      (node (ref "R1") (pin "P$2") (pinfunction "P$2_P$2") (pintype "passive"))
    )
    (net (code "72") (name "Net-(U4-VCC)") (class "Default")
      (node (ref "C20") (pin "P$1") (pinfunction "P$1_P$1") (pintype "passive"))
      (node (ref "U4") (pin "3") (pinfunction "VCC_3") (pintype "power_in"))
    )
    (net (code "73") (name "Net-(U5-CPH)") (class "Default")
      (node (ref "C16") (pin "P$1") (pinfunction "P$1_P$1") (pintype "passive"))
      (node (ref "U5") (pin "2") (pinfunction "CPH_2") (pintype "bidirectional"))
    )
    (net (code "74") (name "Net-(U5-CPL)") (class "Default")
      (node (ref "C16") (pin "P$2") (pinfunction "P$2_P$2") (pintype "passive"))
      (node (ref "U5") (pin "1") (pinfunction "CPL_1") (pintype "bidirectional"))
    )
    (net (code "75") (name "Net-(U5-DVDD)") (class "Default")
      (node (ref "C17") (pin "P$2") (pinfunction "P$2_P$2") (pintype "passive"))
      (node (ref "U5") (pin "38") (pinfunction "DVDD_38") (pintype "bidirectional"))
    )
    (net (code "76") (name "Net-(U5-VCP)") (class "Default")
      (node (ref "C15") (pin "P$2") (pinfunction "P$2_P$2") (pintype "passive"))
      (node (ref "U5") (pin "5") (pinfunction "VCP_5") (pintype "bidirectional"))
    )
    (net (code "77") (name "Net-(U5-VGLS)") (class "Default")
      (node (ref "C38") (pin "P$2") (pinfunction "P$2_P$2") (pintype "passive"))
      (node (ref "U5") (pin "40") (pinfunction "VGLS_40") (pintype "bidirectional"))
    )
    (net (code "78") (name "V+") (class "Default")
      (node (ref "C14") (pin "P$1") (pinfunction "P$1_P$1") (pintype "passive"))
      (node (ref "C15") (pin "P$1") (pinfunction "P$1_P$1") (pintype "passive"))
      (node (ref "C19") (pin "P$1") (pinfunction "P$1_P$1") (pintype "passive"))
      (node (ref "C22") (pin "P$1") (pinfunction "P$1_P$1") (pintype "passive"))
      (node (ref "C23") (pin "P$1") (pinfunction "P$1_P$1") (pintype "passive"))
      (node (ref "C24") (pin "P$1") (pinfunction "P$1_P$1") (pintype "passive"))
      (node (ref "C25") (pin "P$1") (pinfunction "P$1_P$1") (pintype "passive"))
      (node (ref "C26") (pin "P$1") (pinfunction "P$1_P$1") (pintype "passive"))
      (node (ref "C27") (pin "P$1") (pinfunction "P$1_P$1") (pintype "passive"))
      (node (ref "C28") (pin "P$1") (pinfunction "P$1_P$1") (pintype "passive"))
      (node (ref "C29") (pin "P$1") (pinfunction "P$1_P$1") (pintype "passive"))
      (node (ref "C30") (pin "P$1") (pinfunction "P$1_P$1") (pintype "passive"))
      (node (ref "C31") (pin "P$1") (pinfunction "P$1_P$1") (pintype "passive"))
      (node (ref "C32") (pin "P$1") (pinfunction "P$1_P$1") (pintype "passive"))
      (node (ref "C33") (pin "P$1") (pinfunction "P$1_P$1") (pintype "passive"))
      (node (ref "C34") (pin "P$1") (pinfunction "P$1_P$1") (pintype "passive"))
      (node (ref "C35") (pin "P$1") (pinfunction "P$1_P$1") (pintype "passive"))
      (node (ref "C36") (pin "P$1") (pinfunction "P$1_P$1") (pintype "passive"))
      (node (ref "C37") (pin "P$1") (pinfunction "P$1_P$1") (pintype "passive"))
      (node (ref "C39") (pin "P$1") (pinfunction "P$1_P$1") (pintype "passive"))
      (node (ref "C40") (pin "P$1") (pinfunction "P$1_P$1") (pintype "passive"))
      (node (ref "C41") (pin "P$1") (pinfunction "P$1_P$1") (pintype "passive"))
      (node (ref "C42") (pin "P$1") (pinfunction "P$1_P$1") (pintype "passive"))
      (node (ref "C43") (pin "P$1") (pinfunction "P$1_P$1") (pintype "passive"))
      (node (ref "C44") (pin "P$1") (pinfunction "P$1_P$1") (pintype "passive"))
      (node (ref "C45") (pin "P$1") (pinfunction "P$1_P$1") (pintype "passive"))
      (node (ref "C46") (pin "P$1") (pinfunction "P$1_P$1") (pintype "passive"))
      (node (ref "C47") (pin "P$1") (pinfunction "P$1_P$1") (pintype "passive"))
      (node (ref "C48") (pin "P$1") (pinfunction "P$1_P$1") (pintype "passive"))
      (node (ref "C49") (pin "P$1") (pinfunction "P$1_P$1") (pintype "passive"))
      (node (ref "C50") (pin "P$1") (pinfunction "P$1_P$1") (pintype "passive"))
      (node (ref "C51") (pin "P$1") (pinfunction "P$1_P$1") (pintype "passive"))
      (node (ref "C52") (pin "P$1") (pinfunction "P$1_P$1") (pintype "passive"))
      (node (ref "C53") (pin "P$1") (pinfunction "P$1_P$1") (pintype "passive"))
      (node (ref "C54") (pin "P$1") (pinfunction "P$1_P$1") (pintype "passive"))
      (node (ref "C61") (pin "P$1") (pinfunction "P$1_P$1") (pintype "passive"))
      (node (ref "C62") (pin "P$1") (pinfunction "P$1_P$1") (pintype "passive"))
      (node (ref "C63") (pin "P$1") (pinfunction "P$1_P$1") (pintype "passive"))
      (node (ref "J1") (pin "1") (pinfunction "1_1") (pintype "passive"))
      (node (ref "J2") (pin "1") (pinfunction "1_1") (pintype "passive"))
      (node (ref "Q1") (pin "5") (pinfunction "D_5") (pintype "passive"))
      (node (ref "Q1") (pin "6") (pinfunction "D_6") (pintype "passive"))
      (node (ref "Q1") (pin "7") (pinfunction "D_7") (pintype "passive"))
      (node (ref "Q1") (pin "8") (pinfunction "D_8") (pintype "passive"))
      (node (ref "Q1") (pin "PAD") (pinfunction "D_PAD") (pintype "passive"))
      (node (ref "Q3") (pin "5") (pinfunction "D_5") (pintype "passive"))
      (node (ref "Q3") (pin "6") (pinfunction "D_6") (pintype "passive"))
      (node (ref "Q3") (pin "7") (pinfunction "D_7") (pintype "passive"))
      (node (ref "Q3") (pin "8") (pinfunction "D_8") (pintype "passive"))
      (node (ref "Q3") (pin "PAD") (pinfunction "D_PAD") (pintype "passive"))
      (node (ref "Q5") (pin "5") (pinfunction "D_5") (pintype "passive"))
      (node (ref "Q5") (pin "6") (pinfunction "D_6") (pintype "passive"))
      (node (ref "Q5") (pin "7") (pinfunction "D_7") (pintype "passive"))
      (node (ref "Q5") (pin "8") (pinfunction "D_8") (pintype "passive"))
      (node (ref "Q5") (pin "PAD") (pinfunction "D_PAD") (pintype "passive"))
      (node (ref "R5") (pin "P$2") (pinfunction "P$2_P$2") (pintype "passive"))
      (node (ref "U4") (pin "1") (pinfunction "VIN_1") (pintype "input"))
      (node (ref "U4") (pin "2") (pinfunction "EN/UVLO_2") (pintype "input"))
      (node (ref "U5") (pin "3") (pinfunction "VM_3") (pintype "bidirectional"))
      (node (ref "U5") (pin "4") (pinfunction "VDRAIN_4") (pintype "bidirectional"))
    )
    (net (code "79") (name "V-") (class "Default")
      (node (ref "C14") (pin "P$2") (pinfunction "P$2_P$2") (pintype "passive"))
      (node (ref "C17") (pin "P$1") (pinfunction "P$1_P$1") (pintype "passive"))
      (node (ref "C19") (pin "P$2") (pinfunction "P$2_P$2") (pintype "passive"))
      (node (ref "C22") (pin "P$2") (pinfunction "P$2_P$2") (pintype "passive"))
      (node (ref "C23") (pin "P$2") (pinfunction "P$2_P$2") (pintype "passive"))
      (node (ref "C24") (pin "P$2") (pinfunction "P$2_P$2") (pintype "passive"))
      (node (ref "C25") (pin "P$2") (pinfunction "P$2_P$2") (pintype "passive"))
      (node (ref "C26") (pin "P$2") (pinfunction "P$2_P$2") (pintype "passive"))
      (node (ref "C27") (pin "P$2") (pinfunction "P$2_P$2") (pintype "passive"))
      (node (ref "C28") (pin "P$2") (pinfunction "P$2_P$2") (pintype "passive"))
      (node (ref "C29") (pin "P$2") (pinfunction "P$2_P$2") (pintype "passive"))
      (node (ref "C30") (pin "P$2") (pinfunction "P$2_P$2") (pintype "passive"))
      (node (ref "C31") (pin "P$2") (pinfunction "P$2_P$2") (pintype "passive"))
      (node (ref "C32") (pin "P$2") (pinfunction "P$2_P$2") (pintype "passive"))
      (node (ref "C33") (pin "P$2") (pinfunction "P$2_P$2") (pintype "passive"))
      (node (ref "C34") (pin "P$2") (pinfunction "P$2_P$2") (pintype "passive"))
      (node (ref "C35") (pin "P$2") (pinfunction "P$2_P$2") (pintype "passive"))
      (node (ref "C36") (pin "P$2") (pinfunction "P$2_P$2") (pintype "passive"))
      (node (ref "C37") (pin "P$2") (pinfunction "P$2_P$2") (pintype "passive"))
      (node (ref "C38") (pin "P$1") (pinfunction "P$1_P$1") (pintype "passive"))
      (node (ref "C39") (pin "P$2") (pinfunction "P$2_P$2") (pintype "passive"))
      (node (ref "C40") (pin "P$2") (pinfunction "P$2_P$2") (pintype "passive"))
      (node (ref "C41") (pin "P$2") (pinfunction "P$2_P$2") (pintype "passive"))
      (node (ref "C42") (pin "P$2") (pinfunction "P$2_P$2") (pintype "passive"))
      (node (ref "C43") (pin "P$2") (pinfunction "P$2_P$2") (pintype "passive"))
      (node (ref "C44") (pin "P$2") (pinfunction "P$2_P$2") (pintype "passive"))
      (node (ref "C45") (pin "P$2") (pinfunction "P$2_P$2") (pintype "passive"))
      (node (ref "C46") (pin "P$2") (pinfunction "P$2_P$2") (pintype "passive"))
      (node (ref "C47") (pin "P$2") (pinfunction "P$2_P$2") (pintype "passive"))
      (node (ref "C48") (pin "P$2") (pinfunction "P$2_P$2") (pintype "passive"))
      (node (ref "C49") (pin "P$2") (pinfunction "P$2_P$2") (pintype "passive"))
      (node (ref "C50") (pin "P$2") (pinfunction "P$2_P$2") (pintype "passive"))
      (node (ref "C51") (pin "P$2") (pinfunction "P$2_P$2") (pintype "passive"))
      (node (ref "C52") (pin "P$2") (pinfunction "P$2_P$2") (pintype "passive"))
      (node (ref "C53") (pin "P$2") (pinfunction "P$2_P$2") (pintype "passive"))
      (node (ref "C54") (pin "P$2") (pinfunction "P$2_P$2") (pintype "passive"))
      (node (ref "C55") (pin "P$2") (pinfunction "P$2_P$2") (pintype "passive"))
      (node (ref "D1") (pin "2") (pinfunction "A_2") (pintype "bidirectional"))
      (node (ref "D5") (pin "2") (pinfunction "A_2") (pintype "bidirectional"))
      (node (ref "D6") (pin "2") (pinfunction "A_2") (pintype "bidirectional"))
      (node (ref "J1") (pin "2") (pinfunction "2_2") (pintype "passive"))
      (node (ref "J2") (pin "2") (pinfunction "2_2") (pintype "passive"))
      (node (ref "R10") (pin "P$2") (pinfunction "P$2_P$2") (pintype "passive"))
      (node (ref "RA") (pin "1") (pinfunction "1_1") (pintype "passive"))
      (node (ref "RB") (pin "1") (pinfunction "1_1") (pintype "passive"))
      (node (ref "RC") (pin "1") (pinfunction "1_1") (pintype "passive"))
      (node (ref "SH1") (pin "2") (pinfunction "P$2_2") (pintype "bidirectional"))
      (node (ref "SH2") (pin "2") (pinfunction "P$2_2") (pintype "bidirectional"))
      (node (ref "SH3") (pin "2") (pinfunction "P$2_2") (pintype "bidirectional"))
      (node (ref "SH4") (pin "1") (pinfunction "P$1_1") (pintype "bidirectional"))
      (node (ref "U5") (pin "39") (pinfunction "GND_39") (pintype "bidirectional"))
      (node (ref "U5") (pin "P1") (pinfunction "PAD_P1") (pintype "bidirectional"))
      (node (ref "U5") (pin "P12") (pinfunction "PAD_P12") (pintype "bidirectional"))
      (node (ref "U5") (pin "P13") (pinfunction "PAD_P13") (pintype "bidirectional"))
      (node (ref "U5") (pin "P14") (pinfunction "PAD_P14") (pintype "bidirectional"))
      (node (ref "U5") (pin "P17") (pinfunction "PAD_P17") (pintype "bidirectional"))
      (node (ref "U5") (pin "P18") (pinfunction "PAD_P18") (pintype "bidirectional"))
      (node (ref "U5") (pin "P19") (pinfunction "PAD_P19") (pintype "bidirectional"))
      (node (ref "U5") (pin "P2") (pinfunction "PAD_P2") (pintype "bidirectional"))
      (node (ref "U5") (pin "P3") (pinfunction "PAD_P3") (pintype "bidirectional"))
      (node (ref "U5") (pin "P7") (pinfunction "PAD_P7") (pintype "bidirectional"))
      (node (ref "U5") (pin "P8") (pinfunction "PAD_P8") (pintype "bidirectional"))
      (node (ref "U5") (pin "P9") (pinfunction "PAD_P9") (pintype "bidirectional"))
      (node (ref "U5") (pin "PAD") (pinfunction "PAD_PAD") (pintype "bidirectional"))
    )
    (net (code "80") (name "unconnected-(M1-PadP$1)") (class "Default")
      (node (ref "M1") (pin "P$1") (pinfunction "P$1_P$1") (pintype "bidirectional"))
    )
    (net (code "81") (name "unconnected-(M2-PadP$1)") (class "Default")
      (node (ref "M2") (pin "P$1") (pinfunction "P$1_P$1") (pintype "bidirectional"))
    )
    (net (code "82") (name "unconnected-(M4-PadP$1)") (class "Default")
      (node (ref "M4") (pin "P$1") (pinfunction "P$1_P$1") (pintype "bidirectional"))
    )
    (net (code "83") (name "unconnected-(SWD-Pad1)") (class "Default")
      (node (ref "SWD") (pin "1") (pinfunction "1_1") (pintype "passive"))
    )
    (net (code "84") (name "unconnected-(U1-PA15-Pad38)") (class "Default")
      (node (ref "U1") (pin "38") (pinfunction "PA15_38") (pintype "bidirectional"))
    )
    (net (code "85") (name "unconnected-(U1-PB3-Pad41)") (class "Default")
      (node (ref "U1") (pin "41") (pinfunction "PB3_41") (pintype "bidirectional"))
    )
    (net (code "86") (name "unconnected-(U1-PB10-Pad22)") (class "Default")
      (node (ref "U1") (pin "22") (pinfunction "PB10_22") (pintype "bidirectional"))
    )
    (net (code "87") (name "unconnected-(U1-PC6-Pad29)") (class "Default")
      (node (ref "U1") (pin "29") (pinfunction "PC6_29") (pintype "bidirectional"))
    )
    (net (code "88") (name "unconnected-(U3-I-Pad14)") (class "Default")
      (node (ref "U3") (pin "14") (pinfunction "I_14") (pintype "bidirectional"))
    )
    (net (code "89") (name "unconnected-(U3-PWM-Pad8)") (class "Default")
      (node (ref "U3") (pin "8") (pinfunction "PWM_8") (pintype "bidirectional"))
    )
    (net (code "90") (name "unconnected-(U3-VDD5V-Pad11)") (class "Default")
      (node (ref "U3") (pin "11") (pinfunction "VDD5V_11") (pintype "bidirectional"))
    )
    (net (code "91") (name "unconnected-(U4-MODE-Pad5)") (class "Default")
      (node (ref "U4") (pin "5") (pinfunction "MODE_5") (pintype "input"))
    )
    (net (code "92") (name "unconnected-(U4-~{RESET}-Pad6)") (class "Default")
      (node (ref "U4") (pin "6") (pinfunction "~{RESET}_6") (pintype "output"))
    )
  )
)
